# mainboard_edited_newer_edit_removed_most.net
KiCad netlist of a schematic drawn in EAGLE
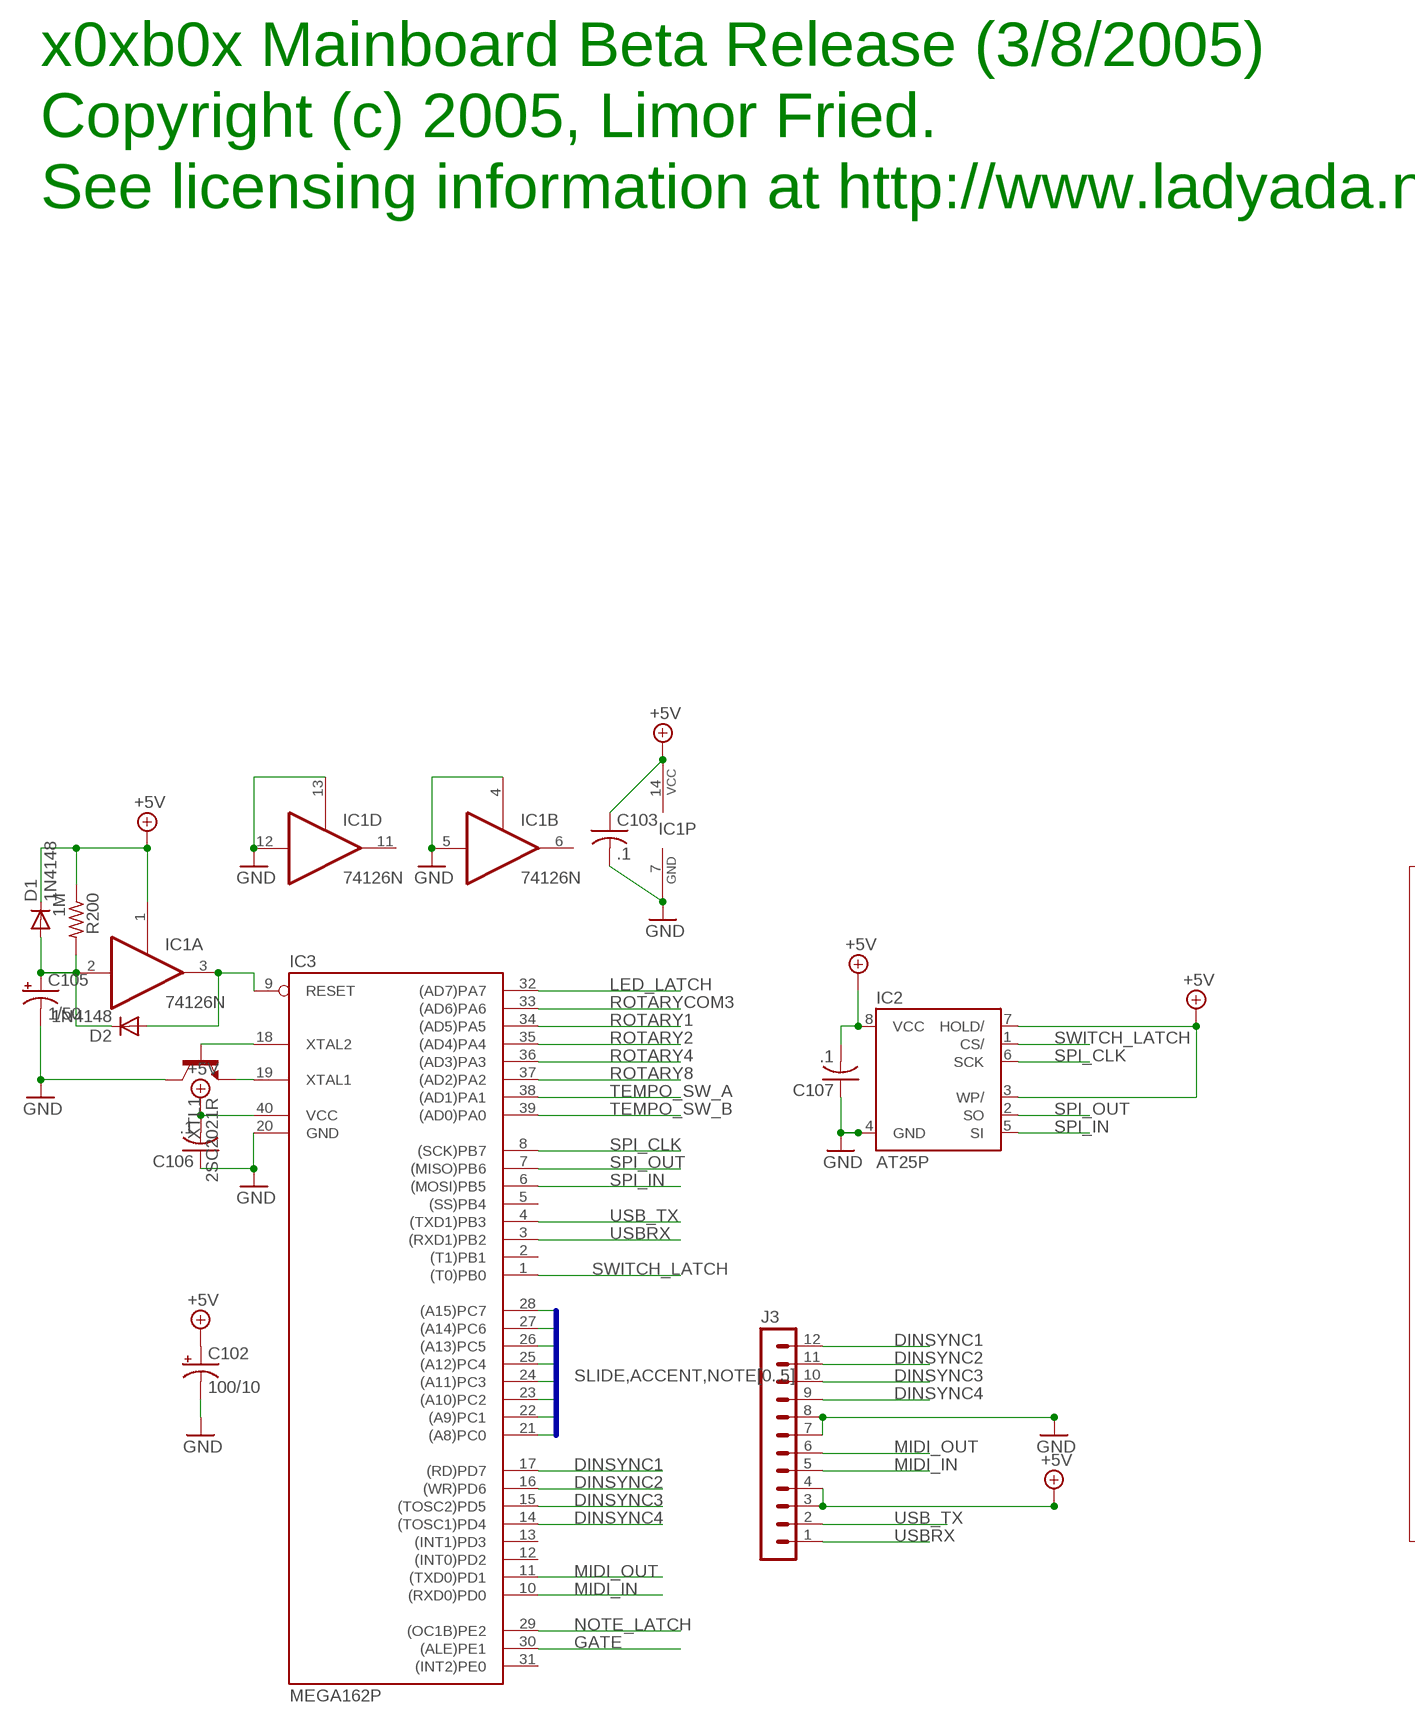
[diagram p0: schematic, sheet 1, part 1 of 3]
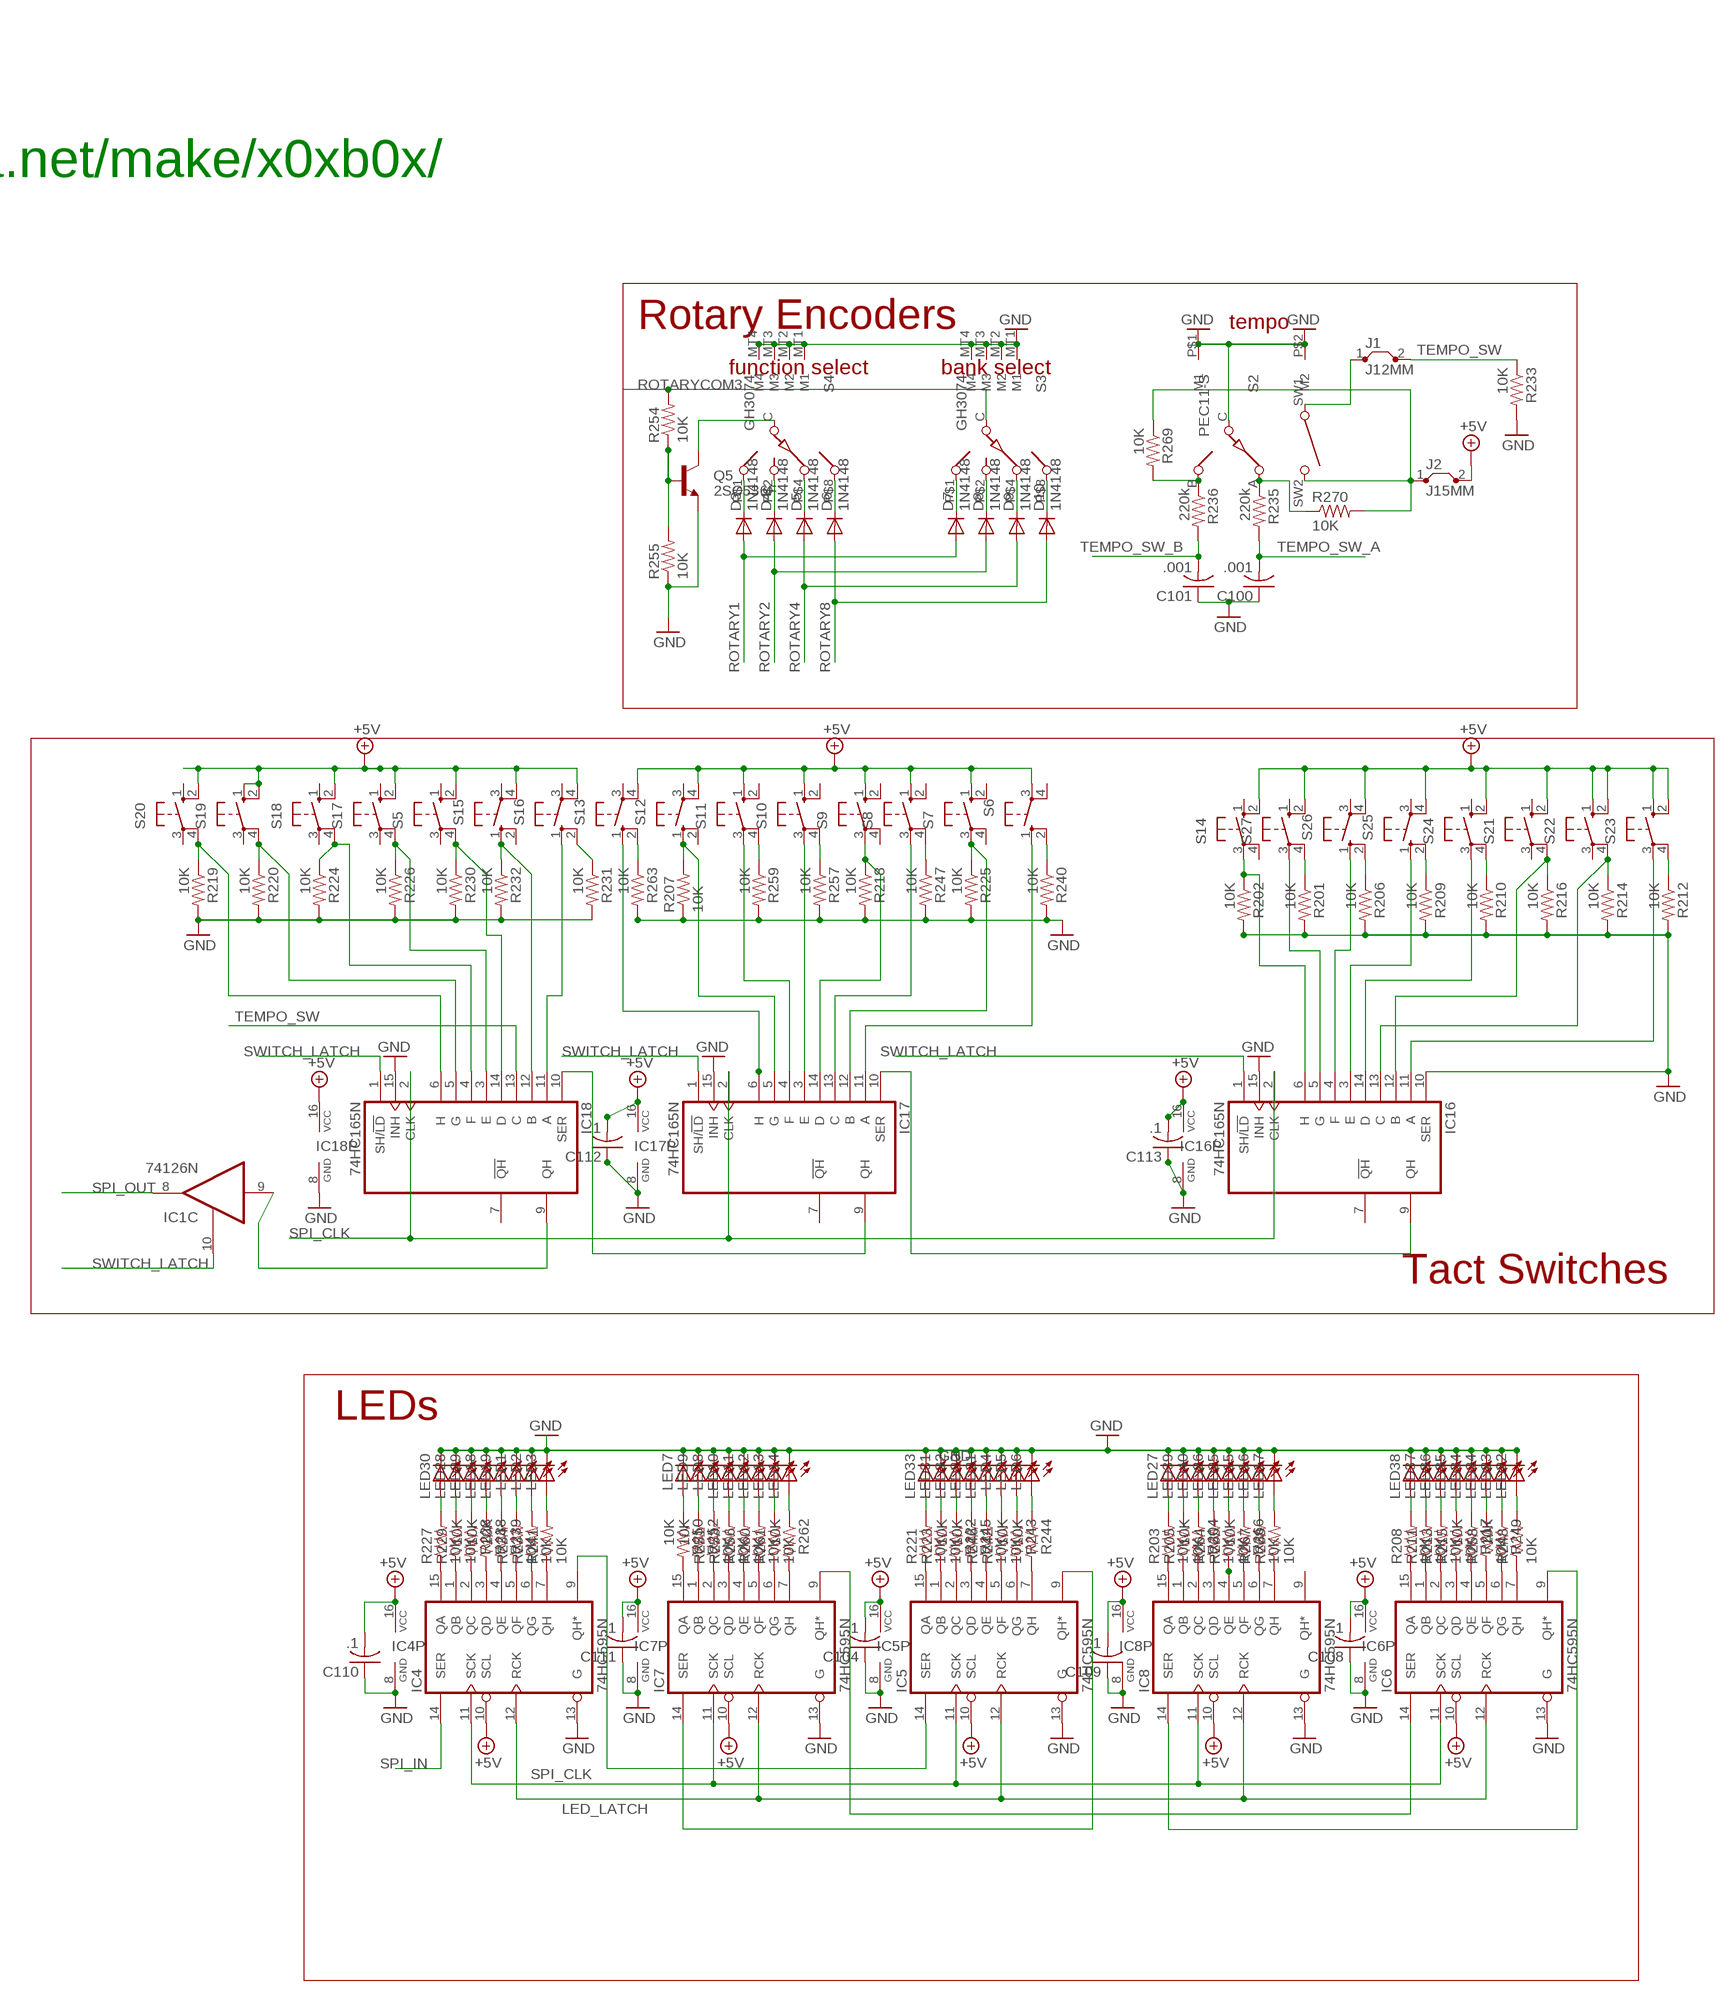
[diagram p1: schematic, sheet 1, part 2 of 3]
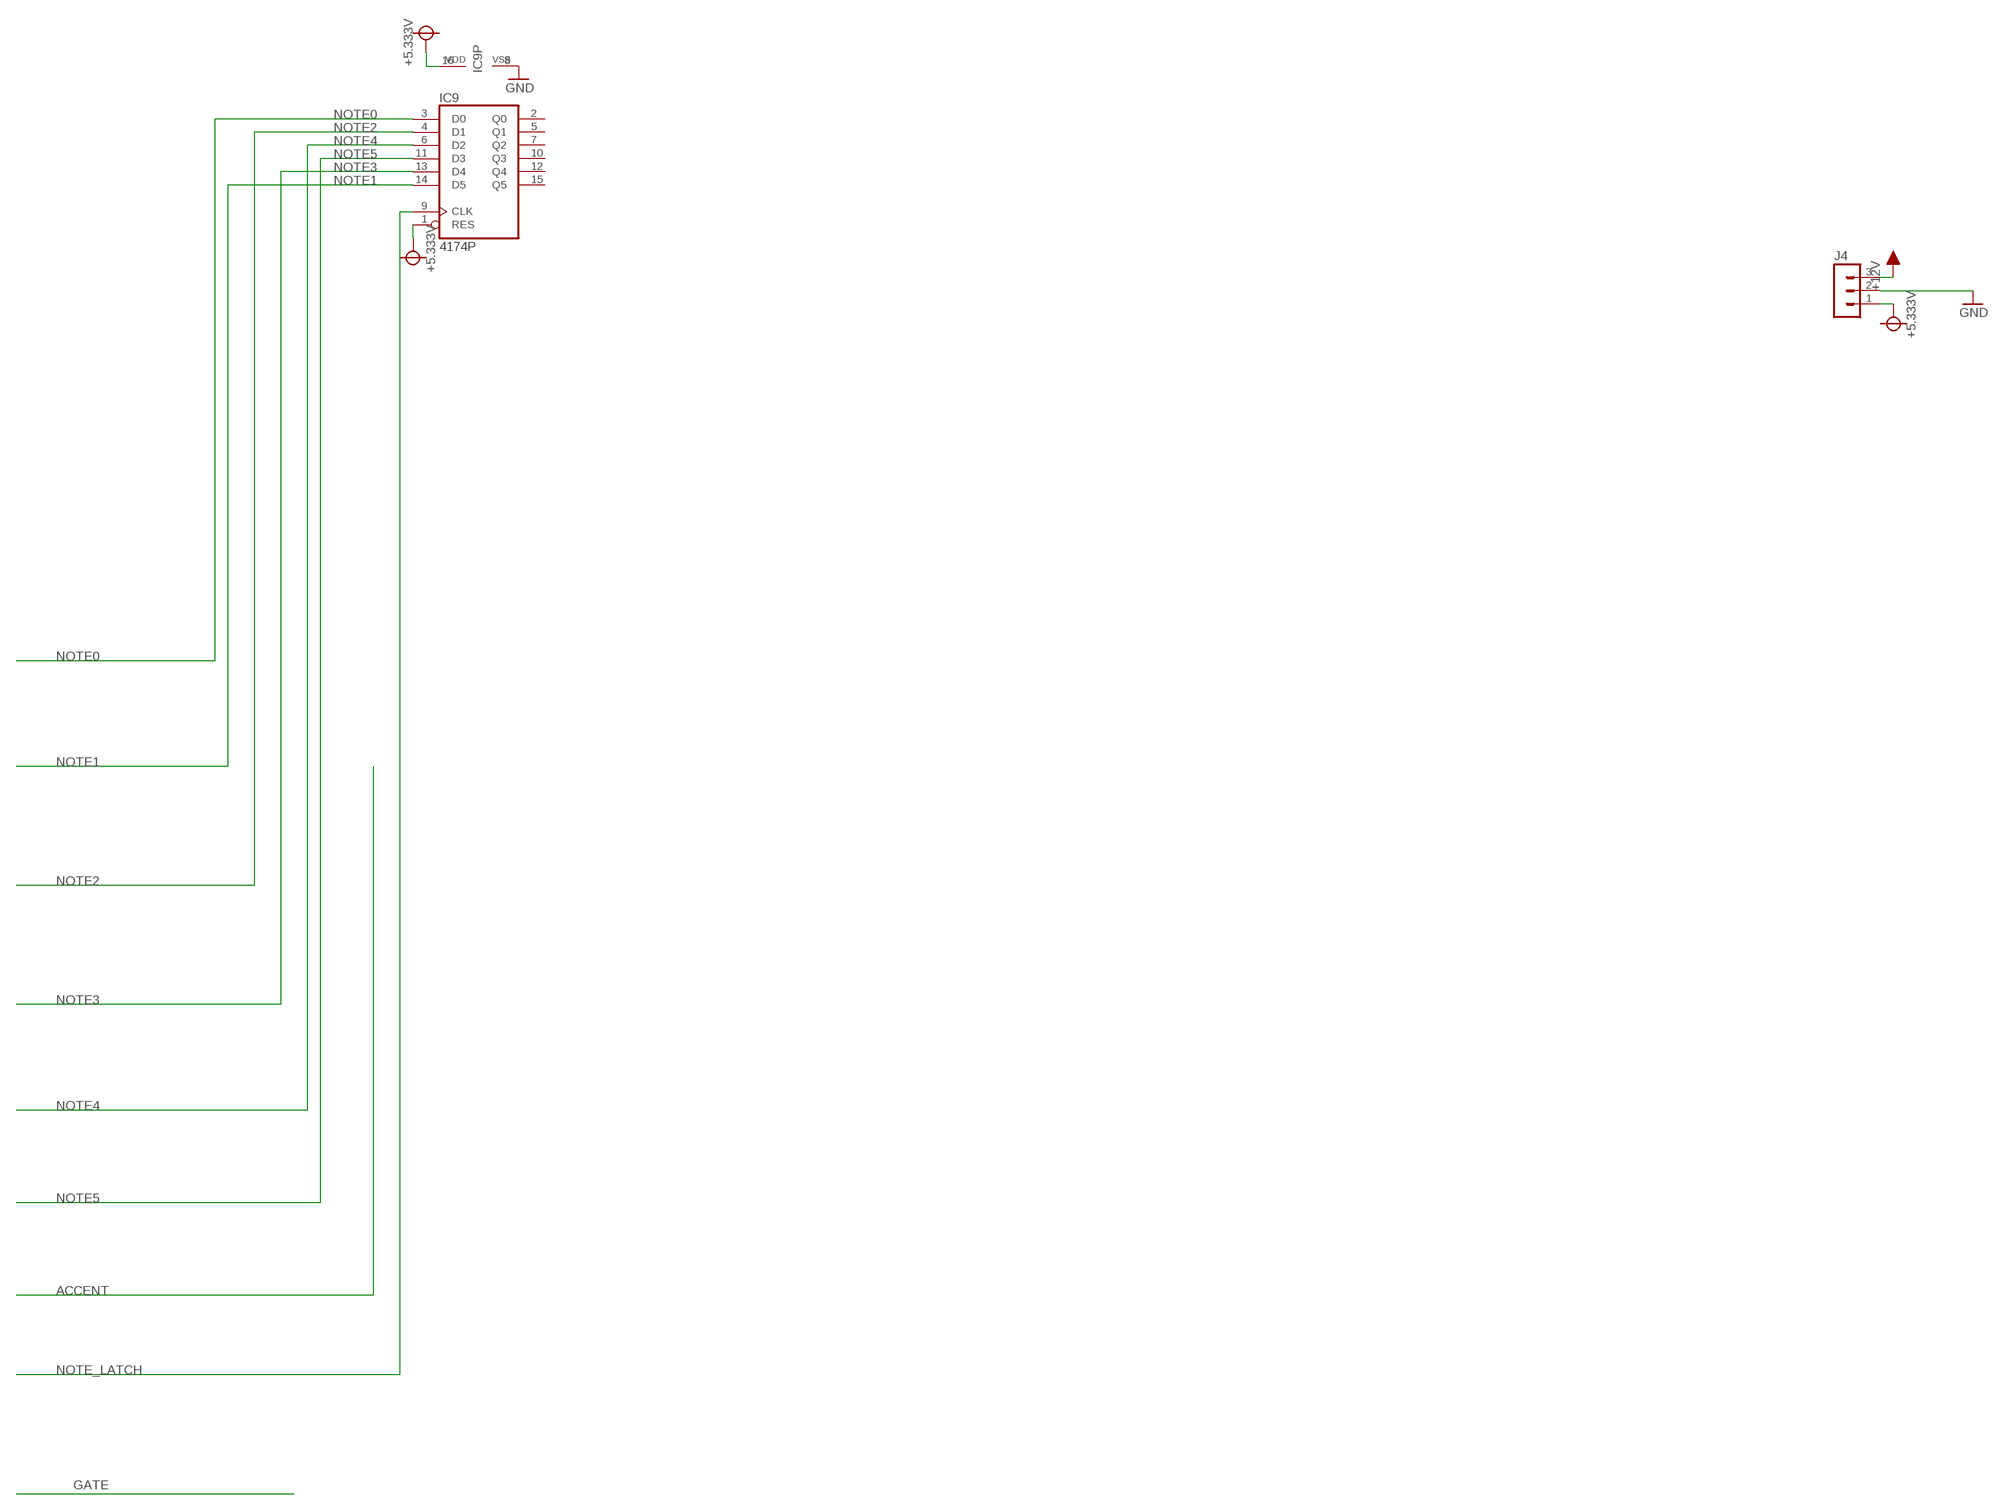
[diagram p2: schematic, sheet 1, part 3 of 3]

(export (version "E")
  (design (tool "Eeschema 10.0.6"))
  (components
    (comp (ref "C100")
      (value ".001")
      (footprint "eagle-import:C050-035X075")
      (libsource (lib "eagle-import") (part "C-US050-035X075"))
    )
    (comp (ref "C101")
      (value ".001")
      (footprint "eagle-import:C050-035X075")
      (libsource (lib "eagle-import") (part "C-US050-035X075"))
    )
    (comp (ref "C102")
      (value "100/10")
      (footprint "eagle-import:E5-6")
      (libsource (lib "eagle-import") (part "CPOL-USE5-6"))
    )
    (comp (ref "C103")
      (value ".1")
      (footprint "eagle-import:C050H075X075")
      (libsource (lib "eagle-import") (part "C-US050H075X075"))
    )
    (comp (ref "C104")
      (value ".1")
      (footprint "eagle-import:C050H075X075")
      (libsource (lib "eagle-import") (part "C-US050H075X075"))
    )
    (comp (ref "C105")
      (value "1/50")
      (footprint "eagle-import:E5-6")
      (libsource (lib "eagle-import") (part "CPOL-USE5-6"))
    )
    (comp (ref "C106")
      (value ".1")
      (footprint "eagle-import:C050H075X075")
      (libsource (lib "eagle-import") (part "C-US050H075X075"))
    )
    (comp (ref "C107")
      (value ".1")
      (footprint "eagle-import:C050H075X075")
      (libsource (lib "eagle-import") (part "C-US050H075X075"))
    )
    (comp (ref "C108")
      (value ".1")
      (footprint "eagle-import:C050H075X075")
      (libsource (lib "eagle-import") (part "C-US050H075X075"))
    )
    (comp (ref "C109")
      (value ".1")
      (footprint "eagle-import:C050H075X075")
      (libsource (lib "eagle-import") (part "C-US050H075X075"))
    )
    (comp (ref "C110")
      (value ".1")
      (footprint "eagle-import:C050H075X075")
      (libsource (lib "eagle-import") (part "C-US050H075X075"))
    )
    (comp (ref "C111")
      (value ".1")
      (footprint "eagle-import:C050H075X075")
      (libsource (lib "eagle-import") (part "C-US050H075X075"))
    )
    (comp (ref "C112")
      (value ".1")
      (footprint "eagle-import:C050H075X075")
      (libsource (lib "eagle-import") (part "C-US050H075X075"))
    )
    (comp (ref "C113")
      (value ".1")
      (footprint "eagle-import:C050H075X075")
      (libsource (lib "eagle-import") (part "C-US050H075X075"))
    )
    (comp (ref "D1")
      (value "1N4148")
      (footprint "eagle-import:DO35-10")
      (libsource (lib "eagle-import") (part "1N4148"))
    )
    (comp (ref "D2")
      (value "1N4148")
      (footprint "eagle-import:DO35-10")
      (libsource (lib "eagle-import") (part "1N4148"))
    )
    (comp (ref "D3")
      (value "1N4148")
      (footprint "eagle-import:DO35-10")
      (libsource (lib "eagle-import") (part "1N4148"))
    )
    (comp (ref "D4")
      (value "1N4148")
      (footprint "eagle-import:DO35-10")
      (libsource (lib "eagle-import") (part "1N4148"))
    )
    (comp (ref "D5")
      (value "1N4148")
      (footprint "eagle-import:DO35-10")
      (libsource (lib "eagle-import") (part "1N4148"))
    )
    (comp (ref "D6")
      (value "1N4148")
      (footprint "eagle-import:DO35-10")
      (libsource (lib "eagle-import") (part "1N4148"))
    )
    (comp (ref "D7")
      (value "1N4148")
      (footprint "eagle-import:DO35-10")
      (libsource (lib "eagle-import") (part "1N4148"))
    )
    (comp (ref "D8")
      (value "1N4148")
      (footprint "eagle-import:DO35-10")
      (libsource (lib "eagle-import") (part "1N4148"))
    )
    (comp (ref "D9")
      (value "1N4148")
      (footprint "eagle-import:DO35-10")
      (libsource (lib "eagle-import") (part "1N4148"))
    )
    (comp (ref "D10")
      (value "1N4148")
      (footprint "eagle-import:DO35-10")
      (libsource (lib "eagle-import") (part "1N4148"))
    )
    (comp (ref "IC1")
      (value "74126N")
      (footprint "eagle-import:DIL14")
      (libsource (lib "eagle-import") (part "74126N"))
    )
    (comp (ref "IC2")
      (value "AT25P")
      (footprint "eagle-import:DIL08")
      (libsource (lib "eagle-import") (part "AT25P"))
    )
    (comp (ref "IC3")
      (value "MEGA162P")
      (footprint "eagle-import:DIL40")
      (libsource (lib "eagle-import") (part "MEGA162P"))
    )
    (comp (ref "IC4")
      (value "74HC595N")
      (footprint "eagle-import:DIL16")
      (libsource (lib "eagle-import") (part "74595NHC"))
    )
    (comp (ref "IC5")
      (value "74HC595N")
      (footprint "eagle-import:DIL16")
      (libsource (lib "eagle-import") (part "74595NHC"))
    )
    (comp (ref "IC6")
      (value "74HC595N")
      (footprint "eagle-import:DIL16")
      (libsource (lib "eagle-import") (part "74595NHC"))
    )
    (comp (ref "IC7")
      (value "74HC595N")
      (footprint "eagle-import:DIL16")
      (libsource (lib "eagle-import") (part "74595NHC"))
    )
    (comp (ref "IC8")
      (value "74HC595N")
      (footprint "eagle-import:DIL16")
      (libsource (lib "eagle-import") (part "74595NHC"))
    )
    (comp (ref "IC9")
      (value "4174P")
      (footprint "eagle-import:DIL16")
      (libsource (lib "eagle-import") (part "4174P"))
    )
    (comp (ref "IC16")
      (value "74HC165N")
      (footprint "eagle-import:DIL16")
      (libsource (lib "eagle-import") (part "74165NHC"))
    )
    (comp (ref "IC17")
      (value "74HC165N")
      (footprint "eagle-import:DIL16")
      (libsource (lib "eagle-import") (part "74165NHC"))
    )
    (comp (ref "IC18")
      (value "74HC165N")
      (footprint "eagle-import:DIL16")
      (libsource (lib "eagle-import") (part "74165NHC"))
    )
    (comp (ref "J1")
      (value "J12MM")
      (footprint "eagle-import:12")
      (libsource (lib "eagle-import") (part "J12MM"))
    )
    (comp (ref "J2")
      (value "J15MM")
      (footprint "eagle-import:15")
      (libsource (lib "eagle-import") (part "J15MM"))
    )
    (comp (ref "J3")
      (value "MA12-1")
      (footprint "eagle-import:MA12-1")
      (libsource (lib "eagle-import") (part "MA12-1"))
    )
    (comp (ref "J4")
      (value "MA03-1")
      (footprint "eagle-import:MA03-1")
      (libsource (lib "eagle-import") (part "MA03-1"))
    )
    (comp (ref "LED1")
      (value "LED5MM")
      (footprint "eagle-import:LED5MM")
      (libsource (lib "eagle-import") (part "LED5MM"))
    )
    (comp (ref "LED2")
      (value "LED5MM")
      (footprint "eagle-import:LED5MM")
      (libsource (lib "eagle-import") (part "LED5MM"))
    )
    (comp (ref "LED3")
      (value "LED5MM")
      (footprint "eagle-import:LED5MM")
      (libsource (lib "eagle-import") (part "LED5MM"))
    )
    (comp (ref "LED4")
      (value "LED5MM")
      (footprint "eagle-import:LED5MM")
      (libsource (lib "eagle-import") (part "LED5MM"))
    )
    (comp (ref "LED5")
      (value "LED5MM")
      (footprint "eagle-import:LED5MM")
      (libsource (lib "eagle-import") (part "LED5MM"))
    )
    (comp (ref "LED6")
      (value "LED5MM")
      (footprint "eagle-import:LED5MM")
      (libsource (lib "eagle-import") (part "LED5MM"))
    )
    (comp (ref "LED7")
      (value "LED5MM")
      (footprint "eagle-import:LED5MM")
      (libsource (lib "eagle-import") (part "LED5MM"))
    )
    (comp (ref "LED8")
      (value "LED5MM")
      (footprint "eagle-import:LED5MM")
      (libsource (lib "eagle-import") (part "LED5MM"))
    )
    (comp (ref "LED9")
      (value "LED5MM")
      (footprint "eagle-import:LED5MM")
      (libsource (lib "eagle-import") (part "LED5MM"))
    )
    (comp (ref "LED10")
      (value "LED5MM")
      (footprint "eagle-import:LED5MM")
      (libsource (lib "eagle-import") (part "LED5MM"))
    )
    (comp (ref "LED11")
      (value "LED5MM")
      (footprint "eagle-import:LED5MM")
      (libsource (lib "eagle-import") (part "LED5MM"))
    )
    (comp (ref "LED12")
      (value "LED5MM")
      (footprint "eagle-import:LED5MM")
      (libsource (lib "eagle-import") (part "LED5MM"))
    )
    (comp (ref "LED13")
      (value "LED5MM")
      (footprint "eagle-import:LED5MM")
      (libsource (lib "eagle-import") (part "LED5MM"))
    )
    (comp (ref "LED14")
      (value "LED5MM")
      (footprint "eagle-import:LED5MM")
      (libsource (lib "eagle-import") (part "LED5MM"))
    )
    (comp (ref "LED15")
      (value "LED5MM")
      (footprint "eagle-import:LED5MM")
      (libsource (lib "eagle-import") (part "LED5MM"))
    )
    (comp (ref "LED16")
      (value "LED5MM")
      (footprint "eagle-import:LED5MM")
      (libsource (lib "eagle-import") (part "LED5MM"))
    )
    (comp (ref "LED17")
      (value "LED5MM")
      (footprint "eagle-import:LED5MM")
      (libsource (lib "eagle-import") (part "LED5MM"))
    )
    (comp (ref "LED18")
      (value "LED5MM")
      (footprint "eagle-import:LED5MM")
      (libsource (lib "eagle-import") (part "LED5MM"))
    )
    (comp (ref "LED19")
      (value "LED5MM")
      (footprint "eagle-import:LED5MM")
      (libsource (lib "eagle-import") (part "LED5MM"))
    )
    (comp (ref "LED20")
      (value "LED5MM")
      (footprint "eagle-import:LED5MM")
      (libsource (lib "eagle-import") (part "LED5MM"))
    )
    (comp (ref "LED21")
      (value "LED5MM")
      (footprint "eagle-import:LED5MM")
      (libsource (lib "eagle-import") (part "LED5MM"))
    )
    (comp (ref "LED22")
      (value "LED5MM")
      (footprint "eagle-import:LED5MM")
      (libsource (lib "eagle-import") (part "LED5MM"))
    )
    (comp (ref "LED23")
      (value "LED5MM")
      (footprint "eagle-import:LED5MM")
      (libsource (lib "eagle-import") (part "LED5MM"))
    )
    (comp (ref "LED24")
      (value "LED5MM")
      (footprint "eagle-import:LED5MM")
      (libsource (lib "eagle-import") (part "LED5MM"))
    )
    (comp (ref "LED25")
      (value "LED5MM")
      (footprint "eagle-import:LED5MM")
      (libsource (lib "eagle-import") (part "LED5MM"))
    )
    (comp (ref "LED26")
      (value "LED5MM")
      (footprint "eagle-import:LED5MM")
      (libsource (lib "eagle-import") (part "LED5MM"))
    )
    (comp (ref "LED27")
      (value "LED5MM")
      (footprint "eagle-import:LED5MM")
      (libsource (lib "eagle-import") (part "LED5MM"))
    )
    (comp (ref "LED28")
      (value "LED5MM")
      (footprint "eagle-import:LED5MM")
      (libsource (lib "eagle-import") (part "LED5MM"))
    )
    (comp (ref "LED29")
      (value "LED5MM")
      (footprint "eagle-import:LED5MM")
      (libsource (lib "eagle-import") (part "LED5MM"))
    )
    (comp (ref "LED30")
      (value "LED5MM")
      (footprint "eagle-import:LED5MM")
      (libsource (lib "eagle-import") (part "LED5MM"))
    )
    (comp (ref "LED31")
      (value "LED5MM")
      (footprint "eagle-import:LED5MM")
      (libsource (lib "eagle-import") (part "LED5MM"))
    )
    (comp (ref "LED32")
      (value "LED5MM")
      (footprint "eagle-import:LED5MM")
      (libsource (lib "eagle-import") (part "LED5MM"))
    )
    (comp (ref "LED33")
      (value "LED5MM")
      (footprint "eagle-import:LED5MM")
      (libsource (lib "eagle-import") (part "LED5MM"))
    )
    (comp (ref "LED34")
      (value "LED5MM")
      (footprint "eagle-import:LED5MM")
      (libsource (lib "eagle-import") (part "LED5MM"))
    )
    (comp (ref "LED35")
      (value "LED5MM")
      (footprint "eagle-import:LED5MM")
      (libsource (lib "eagle-import") (part "LED5MM"))
    )
    (comp (ref "LED36")
      (value "LED5MM")
      (footprint "eagle-import:LED5MM")
      (libsource (lib "eagle-import") (part "LED5MM"))
    )
    (comp (ref "LED37")
      (value "LED5MM")
      (footprint "eagle-import:LED5MM")
      (libsource (lib "eagle-import") (part "LED5MM"))
    )
    (comp (ref "LED38")
      (value "LED5MM")
      (footprint "eagle-import:LED5MM")
      (libsource (lib "eagle-import") (part "LED5MM"))
    )
    (comp (ref "LED39")
      (value "LED5MM")
      (footprint "eagle-import:LED5MM")
      (libsource (lib "eagle-import") (part "LED5MM"))
    )
    (comp (ref "LED40")
      (value "LED5MM")
      (footprint "eagle-import:LED5MM")
      (libsource (lib "eagle-import") (part "LED5MM"))
    )
    (comp (ref "Q5")
      (value "2SC536F")
      (footprint "eagle-import:2SC536F")
      (libsource (lib "eagle-import") (part "2SC536F"))
    )
    (comp (ref "R200")
      (value "1M")
      (footprint "eagle-import:0207_5V")
      (libsource (lib "eagle-import") (part "R-US_0207/5V"))
    )
    (comp (ref "R201")
      (value "10K")
      (footprint "eagle-import:0207_5V")
      (libsource (lib "eagle-import") (part "R-US_0207/5V"))
    )
    (comp (ref "R202")
      (value "10K")
      (footprint "eagle-import:0207_5V")
      (libsource (lib "eagle-import") (part "R-US_0207/5V"))
    )
    (comp (ref "R203")
      (value "10K")
      (footprint "eagle-import:0207_5V")
      (libsource (lib "eagle-import") (part "R-US_0207/5V"))
    )
    (comp (ref "R204")
      (value "10K")
      (footprint "eagle-import:0207_5V")
      (libsource (lib "eagle-import") (part "R-US_0207/5V"))
    )
    (comp (ref "R205")
      (value "10K")
      (footprint "eagle-import:0207_5V")
      (libsource (lib "eagle-import") (part "R-US_0207/5V"))
    )
    (comp (ref "R206")
      (value "10K")
      (footprint "eagle-import:0207_5V")
      (libsource (lib "eagle-import") (part "R-US_0207/5V"))
    )
    (comp (ref "R207")
      (value "10K")
      (footprint "eagle-import:0207_5V")
      (libsource (lib "eagle-import") (part "R-US_0207/5V"))
    )
    (comp (ref "R208")
      (value "10K")
      (footprint "eagle-import:0207_5V")
      (libsource (lib "eagle-import") (part "R-US_0207/5V"))
    )
    (comp (ref "R209")
      (value "10K")
      (footprint "eagle-import:0207_5V")
      (libsource (lib "eagle-import") (part "R-US_0207/5V"))
    )
    (comp (ref "R210")
      (value "10K")
      (footprint "eagle-import:0207_5V")
      (libsource (lib "eagle-import") (part "R-US_0207/5V"))
    )
    (comp (ref "R211")
      (value "10K")
      (footprint "eagle-import:0207_5V")
      (libsource (lib "eagle-import") (part "R-US_0207/5V"))
    )
    (comp (ref "R212")
      (value "10K")
      (footprint "eagle-import:0207_5V")
      (libsource (lib "eagle-import") (part "R-US_0207/5V"))
    )
    (comp (ref "R213")
      (value "10K")
      (footprint "eagle-import:0207_5V")
      (libsource (lib "eagle-import") (part "R-US_0207/5V"))
    )
    (comp (ref "R214")
      (value "10K")
      (footprint "eagle-import:0207_5V")
      (libsource (lib "eagle-import") (part "R-US_0207/5V"))
    )
    (comp (ref "R215")
      (value "10K")
      (footprint "eagle-import:0207_5V")
      (libsource (lib "eagle-import") (part "R-US_0207/5V"))
    )
    (comp (ref "R216")
      (value "10K")
      (footprint "eagle-import:0207_5V")
      (libsource (lib "eagle-import") (part "R-US_0207/5V"))
    )
    (comp (ref "R217")
      (value "10K")
      (footprint "eagle-import:0207_5V")
      (libsource (lib "eagle-import") (part "R-US_0207/5V"))
    )
    (comp (ref "R218")
      (value "10K")
      (footprint "eagle-import:0207_5V")
      (libsource (lib "eagle-import") (part "R-US_0207/5V"))
    )
    (comp (ref "R219")
      (value "10K")
      (footprint "eagle-import:0207_5V")
      (libsource (lib "eagle-import") (part "R-US_0207/5V"))
    )
    (comp (ref "R220")
      (value "10K")
      (footprint "eagle-import:0207_5V")
      (libsource (lib "eagle-import") (part "R-US_0207/5V"))
    )
    (comp (ref "R221")
      (value "10K")
      (footprint "eagle-import:0207_5V")
      (libsource (lib "eagle-import") (part "R-US_0207/5V"))
    )
    (comp (ref "R222")
      (value "10K")
      (footprint "eagle-import:0207_5V")
      (libsource (lib "eagle-import") (part "R-US_0207/5V"))
    )
    (comp (ref "R223")
      (value "10K")
      (footprint "eagle-import:0207_5V")
      (libsource (lib "eagle-import") (part "R-US_0207/5V"))
    )
    (comp (ref "R224")
      (value "10K")
      (footprint "eagle-import:0207_5V")
      (libsource (lib "eagle-import") (part "R-US_0207/5V"))
    )
    (comp (ref "R225")
      (value "10K")
      (footprint "eagle-import:0207_5V")
      (libsource (lib "eagle-import") (part "R-US_0207/5V"))
    )
    (comp (ref "R226")
      (value "10K")
      (footprint "eagle-import:0207_5V")
      (libsource (lib "eagle-import") (part "R-US_0207/5V"))
    )
    (comp (ref "R227")
      (value "10K")
      (footprint "eagle-import:0207_5V")
      (libsource (lib "eagle-import") (part "R-US_0207/5V"))
    )
    (comp (ref "R228")
      (value "10K")
      (footprint "eagle-import:0207_5V")
      (libsource (lib "eagle-import") (part "R-US_0207/5V"))
    )
    (comp (ref "R229")
      (value "10K")
      (footprint "eagle-import:0207_5V")
      (libsource (lib "eagle-import") (part "R-US_0207/5V"))
    )
    (comp (ref "R230")
      (value "10K")
      (footprint "eagle-import:0207_5V")
      (libsource (lib "eagle-import") (part "R-US_0207/5V"))
    )
    (comp (ref "R231")
      (value "10K")
      (footprint "eagle-import:0207_5V")
      (libsource (lib "eagle-import") (part "R-US_0207/5V"))
    )
    (comp (ref "R232")
      (value "10K")
      (footprint "eagle-import:0207_10")
      (libsource (lib "eagle-import") (part "R-US_0207/10"))
    )
    (comp (ref "R233")
      (value "10K")
      (footprint "eagle-import:0207_5V")
      (libsource (lib "eagle-import") (part "R-US_0207/5V"))
    )
    (comp (ref "R234")
      (value "10K")
      (footprint "eagle-import:0207_15")
      (libsource (lib "eagle-import") (part "R-US_0207/15"))
    )
    (comp (ref "R235")
      (value "220k")
      (footprint "eagle-import:0207_5V")
      (libsource (lib "eagle-import") (part "R-US_0207/5V"))
    )
    (comp (ref "R236")
      (value "220k")
      (footprint "eagle-import:0207_5V")
      (libsource (lib "eagle-import") (part "R-US_0207/5V"))
    )
    (comp (ref "R237")
      (value "10K")
      (footprint "eagle-import:0207_5V")
      (libsource (lib "eagle-import") (part "R-US_0207/5V"))
    )
    (comp (ref "R238")
      (value "10K")
      (footprint "eagle-import:0207_5V")
      (libsource (lib "eagle-import") (part "R-US_0207/5V"))
    )
    (comp (ref "R239")
      (value "10K")
      (footprint "eagle-import:0207_5V")
      (libsource (lib "eagle-import") (part "R-US_0207/5V"))
    )
    (comp (ref "R240")
      (value "10K")
      (footprint "eagle-import:0207_5V")
      (libsource (lib "eagle-import") (part "R-US_0207/5V"))
    )
    (comp (ref "R241")
      (value "10K")
      (footprint "eagle-import:0207_5V")
      (libsource (lib "eagle-import") (part "R-US_0207/5V"))
    )
    (comp (ref "R242")
      (value "10K")
      (footprint "eagle-import:0207_5V")
      (libsource (lib "eagle-import") (part "R-US_0207/5V"))
    )
    (comp (ref "R243")
      (value "10K")
      (footprint "eagle-import:0207_5V")
      (libsource (lib "eagle-import") (part "R-US_0207/5V"))
    )
    (comp (ref "R244")
      (value "10K")
      (footprint "eagle-import:0207_5V")
      (libsource (lib "eagle-import") (part "R-US_0207/5V"))
    )
    (comp (ref "R245")
      (value "10K")
      (footprint "eagle-import:0207_5V")
      (libsource (lib "eagle-import") (part "R-US_0207/5V"))
    )
    (comp (ref "R246")
      (value "10K")
      (footprint "eagle-import:0207_5V")
      (libsource (lib "eagle-import") (part "R-US_0207/5V"))
    )
    (comp (ref "R247")
      (value "10K")
      (footprint "eagle-import:0207_5V")
      (libsource (lib "eagle-import") (part "R-US_0207/5V"))
    )
    (comp (ref "R248")
      (value "10K")
      (footprint "eagle-import:0207_5V")
      (libsource (lib "eagle-import") (part "R-US_0207/5V"))
    )
    (comp (ref "R249")
      (value "10K")
      (footprint "eagle-import:0207_5V")
      (libsource (lib "eagle-import") (part "R-US_0207/5V"))
    )
    (comp (ref "R250")
      (value "10K")
      (footprint "eagle-import:0207_5V")
      (libsource (lib "eagle-import") (part "R-US_0207/5V"))
    )
    (comp (ref "R251")
      (value "10K")
      (footprint "eagle-import:0207_5V")
      (libsource (lib "eagle-import") (part "R-US_0207/5V"))
    )
    (comp (ref "R252")
      (value "10K")
      (footprint "eagle-import:0207_5V")
      (libsource (lib "eagle-import") (part "R-US_0207/5V"))
    )
    (comp (ref "R253")
      (value "10K")
      (footprint "eagle-import:0207_5V")
      (libsource (lib "eagle-import") (part "R-US_0207/5V"))
    )
    (comp (ref "R254")
      (value "10K")
      (footprint "eagle-import:0207_5V")
      (libsource (lib "eagle-import") (part "R-US_0207/5V"))
    )
    (comp (ref "R255")
      (value "10K")
      (footprint "eagle-import:0207_5V")
      (libsource (lib "eagle-import") (part "R-US_0207/5V"))
    )
    (comp (ref "R256")
      (value "10K")
      (footprint "eagle-import:0207_5V")
      (libsource (lib "eagle-import") (part "R-US_0207/5V"))
    )
    (comp (ref "R257")
      (value "10K")
      (footprint "eagle-import:0207_5V")
      (libsource (lib "eagle-import") (part "R-US_0207/5V"))
    )
    (comp (ref "R258")
      (value "10K")
      (footprint "eagle-import:0207_5V")
      (libsource (lib "eagle-import") (part "R-US_0207/5V"))
    )
    (comp (ref "R259")
      (value "10K")
      (footprint "eagle-import:0207_5V")
      (libsource (lib "eagle-import") (part "R-US_0207/5V"))
    )
    (comp (ref "R260")
      (value "10K")
      (footprint "eagle-import:0207_5V")
      (libsource (lib "eagle-import") (part "R-US_0207/5V"))
    )
    (comp (ref "R261")
      (value "10K")
      (footprint "eagle-import:0207_5V")
      (libsource (lib "eagle-import") (part "R-US_0207/5V"))
    )
    (comp (ref "R262")
      (value "10K")
      (footprint "eagle-import:0207_5V")
      (libsource (lib "eagle-import") (part "R-US_0207/5V"))
    )
    (comp (ref "R263")
      (value "10K")
      (footprint "eagle-import:0207_5V")
      (libsource (lib "eagle-import") (part "R-US_0207/5V"))
    )
    (comp (ref "R264")
      (value "10K")
      (footprint "eagle-import:0207_5V")
      (libsource (lib "eagle-import") (part "R-US_0207/5V"))
    )
    (comp (ref "R265")
      (value "10K")
      (footprint "eagle-import:0207_5V")
      (libsource (lib "eagle-import") (part "R-US_0207/5V"))
    )
    (comp (ref "R266")
      (value "10K")
      (footprint "eagle-import:0207_5V")
      (libsource (lib "eagle-import") (part "R-US_0207/5V"))
    )
    (comp (ref "R267")
      (value "10K")
      (footprint "eagle-import:0207_5V")
      (libsource (lib "eagle-import") (part "R-US_0207/5V"))
    )
    (comp (ref "R268")
      (value "10K")
      (footprint "eagle-import:0207_5V")
      (libsource (lib "eagle-import") (part "R-US_0207/5V"))
    )
    (comp (ref "R269")
      (value "10K")
      (footprint "eagle-import:0207_5V")
      (libsource (lib "eagle-import") (part "R-US_0207/5V"))
    )
    (comp (ref "R270")
      (value "10K")
      (footprint "eagle-import:0207_5V")
      (libsource (lib "eagle-import") (part "R-US_0207/5V"))
    )
    (comp (ref "S2")
      (value "PEC11-S")
      (footprint "eagle-import:PEC11-S")
      (libsource (lib "eagle-import") (part "PEC11-S"))
    )
    (comp (ref "S3")
      (value "GH3074")
      (footprint "eagle-import:GH3074")
      (libsource (lib "eagle-import") (part "GH3074"))
    )
    (comp (ref "S4")
      (value "GH3074")
      (footprint "eagle-import:GH3074")
      (libsource (lib "eagle-import") (part "GH3074"))
    )
    (comp (ref "S5")
      (value "40-XX")
      (footprint "eagle-import:B3F-40XX")
      (libsource (lib "eagle-import") (part "40-XX"))
    )
    (comp (ref "S6")
      (value "40-XX")
      (footprint "eagle-import:B3F-40XX")
      (libsource (lib "eagle-import") (part "40-XX"))
    )
    (comp (ref "S7")
      (value "40-XX")
      (footprint "eagle-import:B3F-40XX")
      (libsource (lib "eagle-import") (part "40-XX"))
    )
    (comp (ref "S8")
      (value "40-XX")
      (footprint "eagle-import:B3F-40XX")
      (libsource (lib "eagle-import") (part "40-XX"))
    )
    (comp (ref "S9")
      (value "40-XX")
      (footprint "eagle-import:B3F-40XX")
      (libsource (lib "eagle-import") (part "40-XX"))
    )
    (comp (ref "S10")
      (value "40-XX")
      (footprint "eagle-import:B3F-40XX")
      (libsource (lib "eagle-import") (part "40-XX"))
    )
    (comp (ref "S11")
      (value "40-XX")
      (footprint "eagle-import:B3F-40XX")
      (libsource (lib "eagle-import") (part "40-XX"))
    )
    (comp (ref "S12")
      (value "40-XX")
      (footprint "eagle-import:B3F-40XX")
      (libsource (lib "eagle-import") (part "40-XX"))
    )
    (comp (ref "S13")
      (value "40-XX")
      (footprint "eagle-import:B3F-40XX")
      (libsource (lib "eagle-import") (part "40-XX"))
    )
    (comp (ref "S14")
      (value "40-XX")
      (footprint "eagle-import:B3F-40XX")
      (libsource (lib "eagle-import") (part "40-XX"))
    )
    (comp (ref "S15")
      (value "40-XX")
      (footprint "eagle-import:B3F-40XX")
      (libsource (lib "eagle-import") (part "40-XX"))
    )
    (comp (ref "S16")
      (value "40-XX")
      (footprint "eagle-import:B3F-40XX")
      (libsource (lib "eagle-import") (part "40-XX"))
    )
    (comp (ref "S17")
      (value "40-XX")
      (footprint "eagle-import:B3F-40XX")
      (libsource (lib "eagle-import") (part "40-XX"))
    )
    (comp (ref "S18")
      (value "40-XX")
      (footprint "eagle-import:B3F-40XX")
      (libsource (lib "eagle-import") (part "40-XX"))
    )
    (comp (ref "S19")
      (value "40-XX")
      (footprint "eagle-import:B3F-40XX")
      (libsource (lib "eagle-import") (part "40-XX"))
    )
    (comp (ref "S20")
      (value "40-XX")
      (footprint "eagle-import:B3F-40XX")
      (libsource (lib "eagle-import") (part "40-XX"))
    )
    (comp (ref "S21")
      (value "40-XX")
      (footprint "eagle-import:B3F-40XX")
      (libsource (lib "eagle-import") (part "40-XX"))
    )
    (comp (ref "S22")
      (value "40-XX")
      (footprint "eagle-import:B3F-40XX")
      (libsource (lib "eagle-import") (part "40-XX"))
    )
    (comp (ref "S23")
      (value "40-XX")
      (footprint "eagle-import:B3F-40XX")
      (libsource (lib "eagle-import") (part "40-XX"))
    )
    (comp (ref "S24")
      (value "40-XX")
      (footprint "eagle-import:B3F-40XX")
      (libsource (lib "eagle-import") (part "40-XX"))
    )
    (comp (ref "S25")
      (value "40-XX")
      (footprint "eagle-import:B3F-40XX")
      (libsource (lib "eagle-import") (part "40-XX"))
    )
    (comp (ref "S26")
      (value "40-XX")
      (footprint "eagle-import:B3F-40XX")
      (libsource (lib "eagle-import") (part "40-XX"))
    )
    (comp (ref "S27")
      (value "40-XX")
      (footprint "eagle-import:B3F-40XX")
      (libsource (lib "eagle-import") (part "40-XX"))
    )
    (comp (ref "XTL1")
      (value "2SC2021R")
      (footprint "eagle-import:2SC2021")
      (libsource (lib "eagle-import") (part "2SC2021R"))
    )
  )
  (nets
    (net (code "7") (name "+5.333V") (class "Default")
      (node (ref "IC9") (pin "1") (pinfunction "RES_1") (pintype "input"))
      (node (ref "IC9") (pin "16") (pinfunction "VDD_16") (pintype "power_in"))
      (node (ref "J4") (pin "1") (pinfunction "1_1") (pintype "passive"))
    )
    (net (code "8") (name "+5V") (class "Default")
      (node (ref "C102") (pin "+") (pinfunction "+_+") (pintype "passive"))
      (node (ref "C103") (pin "1") (pinfunction "1_1") (pintype "passive"))
      (node (ref "C104") (pin "2") (pinfunction "2_2") (pintype "passive"))
      (node (ref "C106") (pin "2") (pinfunction "2_2") (pintype "passive"))
      (node (ref "C107") (pin "2") (pinfunction "2_2") (pintype "passive"))
      (node (ref "C108") (pin "2") (pinfunction "2_2") (pintype "passive"))
      (node (ref "C109") (pin "2") (pinfunction "2_2") (pintype "passive"))
      (node (ref "C110") (pin "2") (pinfunction "2_2") (pintype "passive"))
      (node (ref "C111") (pin "2") (pinfunction "2_2") (pintype "passive"))
      (node (ref "C112") (pin "2") (pinfunction "2_2") (pintype "passive"))
      (node (ref "C113") (pin "2") (pinfunction "2_2") (pintype "passive"))
      (node (ref "D1") (pin "C") (pinfunction "C_C") (pintype "passive"))
      (node (ref "IC1") (pin "1") (pinfunction "OE_1") (pintype "input"))
      (node (ref "IC1") (pin "14") (pinfunction "VCC_14") (pintype "power_in"))
      (node (ref "IC16") (pin "16") (pinfunction "VCC_16") (pintype "power_in"))
      (node (ref "IC17") (pin "16") (pinfunction "VCC_16") (pintype "power_in"))
      (node (ref "IC18") (pin "16") (pinfunction "VCC_16") (pintype "power_in"))
      (node (ref "IC2") (pin "3") (pinfunction "WP/_3") (pintype "input"))
      (node (ref "IC2") (pin "7") (pinfunction "HOLD/_7") (pintype "input"))
      (node (ref "IC2") (pin "8") (pinfunction "VCC_8") (pintype "power_in"))
      (node (ref "IC3") (pin "40") (pinfunction "VCC_40") (pintype "power_in"))
      (node (ref "IC4") (pin "10") (pinfunction "SCL_10") (pintype "input"))
      (node (ref "IC4") (pin "16") (pinfunction "VCC_16") (pintype "power_in"))
      (node (ref "IC5") (pin "10") (pinfunction "SCL_10") (pintype "input"))
      (node (ref "IC5") (pin "16") (pinfunction "VCC_16") (pintype "power_in"))
      (node (ref "IC6") (pin "10") (pinfunction "SCL_10") (pintype "input"))
      (node (ref "IC6") (pin "16") (pinfunction "VCC_16") (pintype "power_in"))
      (node (ref "IC7") (pin "10") (pinfunction "SCL_10") (pintype "input"))
      (node (ref "IC7") (pin "16") (pinfunction "VCC_16") (pintype "power_in"))
      (node (ref "IC8") (pin "10") (pinfunction "SCL_10") (pintype "input"))
      (node (ref "IC8") (pin "16") (pinfunction "VCC_16") (pintype "power_in"))
      (node (ref "J2") (pin "2") (pinfunction "2_2") (pintype "passive"))
      (node (ref "J3") (pin "3") (pinfunction "3_3") (pintype "passive"))
      (node (ref "J3") (pin "4") (pinfunction "4_4") (pintype "passive"))
      (node (ref "R200") (pin "1") (pinfunction "1_1") (pintype "passive"))
      (node (ref "S10") (pin "1") (pinfunction "S_1") (pintype "passive"))
      (node (ref "S11") (pin "1") (pinfunction "S_1") (pintype "passive"))
      (node (ref "S12") (pin "4") (pinfunction "P1_4") (pintype "passive"))
      (node (ref "S13") (pin "4") (pinfunction "P1_4") (pintype "passive"))
      (node (ref "S14") (pin "2") (pinfunction "S1_2") (pintype "passive"))
      (node (ref "S15") (pin "4") (pinfunction "P1_4") (pintype "passive"))
      (node (ref "S16") (pin "4") (pinfunction "P1_4") (pintype "passive"))
      (node (ref "S17") (pin "2") (pinfunction "S1_2") (pintype "passive"))
      (node (ref "S18") (pin "2") (pinfunction "S1_2") (pintype "passive"))
      (node (ref "S19") (pin "1") (pinfunction "S_1") (pintype "passive"))
      (node (ref "S19") (pin "2") (pinfunction "S1_2") (pintype "passive"))
      (node (ref "S20") (pin "2") (pinfunction "S1_2") (pintype "passive"))
      (node (ref "S21") (pin "2") (pinfunction "S1_2") (pintype "passive"))
      (node (ref "S22") (pin "1") (pinfunction "S_1") (pintype "passive"))
      (node (ref "S22") (pin "2") (pinfunction "S1_2") (pintype "passive"))
      (node (ref "S23") (pin "1") (pinfunction "S_1") (pintype "passive"))
      (node (ref "S23") (pin "2") (pinfunction "S1_2") (pintype "passive"))
      (node (ref "S24") (pin "2") (pinfunction "S1_2") (pintype "passive"))
      (node (ref "S25") (pin "4") (pinfunction "P1_4") (pintype "passive"))
      (node (ref "S26") (pin "4") (pinfunction "P1_4") (pintype "passive"))
      (node (ref "S27") (pin "2") (pinfunction "S1_2") (pintype "passive"))
      (node (ref "S5") (pin "2") (pinfunction "S1_2") (pintype "passive"))
      (node (ref "S6") (pin "3") (pinfunction "P_3") (pintype "passive"))
      (node (ref "S7") (pin "1") (pinfunction "S_1") (pintype "passive"))
      (node (ref "S8") (pin "1") (pinfunction "S_1") (pintype "passive"))
      (node (ref "S9") (pin "1") (pinfunction "S_1") (pintype "passive"))
    )
    (net (code "9") (name "+12V") (class "Default")
      (node (ref "J4") (pin "3") (pinfunction "3_3") (pintype "passive"))
    )
    (net (code "10") (name "/ACCENT") (class "Default")
      (node (ref "IC3") (pin "28") (pinfunction "(A15)PC7_28") (pintype "bidirectional"))
    )
    (net (code "11") (name "/DINSYNC1") (class "Default")
      (node (ref "IC3") (pin "17") (pinfunction "(RD)PD7_17") (pintype "bidirectional"))
      (node (ref "J3") (pin "12") (pinfunction "12_12") (pintype "passive"))
    )
    (net (code "12") (name "/DINSYNC2") (class "Default")
      (node (ref "IC3") (pin "16") (pinfunction "(WR)PD6_16") (pintype "bidirectional"))
      (node (ref "J3") (pin "11") (pinfunction "11_11") (pintype "passive"))
    )
    (net (code "13") (name "/DINSYNC3") (class "Default")
      (node (ref "IC3") (pin "15") (pinfunction "(TOSC2)PD5_15") (pintype "bidirectional"))
      (node (ref "J3") (pin "10") (pinfunction "10_10") (pintype "passive"))
    )
    (net (code "14") (name "/DINSYNC4") (class "Default")
      (node (ref "IC3") (pin "14") (pinfunction "(TOSC1)PD4_14") (pintype "bidirectional"))
      (node (ref "J3") (pin "9") (pinfunction "9_9") (pintype "passive"))
    )
    (net (code "15") (name "/GATE") (class "Default")
      (node (ref "IC3") (pin "30") (pinfunction "(ALE)PE1_30") (pintype "bidirectional"))
    )
    (net (code "16") (name "/LED_LATCH") (class "Default")
      (node (ref "IC3") (pin "32") (pinfunction "(AD7)PA7_32") (pintype "bidirectional"))
      (node (ref "IC4") (pin "12") (pinfunction "RCK_12") (pintype "input"))
      (node (ref "IC5") (pin "12") (pinfunction "RCK_12") (pintype "input"))
      (node (ref "IC6") (pin "12") (pinfunction "RCK_12") (pintype "input"))
      (node (ref "IC7") (pin "12") (pinfunction "RCK_12") (pintype "input"))
      (node (ref "IC8") (pin "12") (pinfunction "RCK_12") (pintype "input"))
    )
    (net (code "17") (name "/MIDI_IN") (class "Default")
      (node (ref "IC3") (pin "10") (pinfunction "(RXD0)PD0_10") (pintype "bidirectional"))
      (node (ref "J3") (pin "5") (pinfunction "5_5") (pintype "passive"))
    )
    (net (code "18") (name "/MIDI_OUT") (class "Default")
      (node (ref "IC3") (pin "11") (pinfunction "(TXD0)PD1_11") (pintype "bidirectional"))
      (node (ref "J3") (pin "6") (pinfunction "6_6") (pintype "passive"))
    )
    (net (code "19") (name "/NOTE0") (class "Default")
      (node (ref "IC3") (pin "21") (pinfunction "(A8)PC0_21") (pintype "bidirectional"))
      (node (ref "IC9") (pin "3") (pinfunction "D0_3") (pintype "input"))
    )
    (net (code "20") (name "/NOTE1") (class "Default")
      (node (ref "IC3") (pin "22") (pinfunction "(A9)PC1_22") (pintype "bidirectional"))
      (node (ref "IC9") (pin "14") (pinfunction "D5_14") (pintype "input"))
    )
    (net (code "21") (name "/NOTE2") (class "Default")
      (node (ref "IC3") (pin "23") (pinfunction "(A10)PC2_23") (pintype "bidirectional"))
      (node (ref "IC9") (pin "4") (pinfunction "D1_4") (pintype "input"))
    )
    (net (code "22") (name "/NOTE3") (class "Default")
      (node (ref "IC3") (pin "24") (pinfunction "(A11)PC3_24") (pintype "bidirectional"))
      (node (ref "IC9") (pin "13") (pinfunction "D4_13") (pintype "input"))
    )
    (net (code "23") (name "/NOTE4") (class "Default")
      (node (ref "IC3") (pin "25") (pinfunction "(A12)PC4_25") (pintype "bidirectional"))
      (node (ref "IC9") (pin "6") (pinfunction "D2_6") (pintype "input"))
    )
    (net (code "24") (name "/NOTE5") (class "Default")
      (node (ref "IC3") (pin "26") (pinfunction "(A13)PC5_26") (pintype "bidirectional"))
      (node (ref "IC9") (pin "11") (pinfunction "D3_11") (pintype "input"))
    )
    (net (code "25") (name "/NOTE_LATCH") (class "Default")
      (node (ref "IC3") (pin "29") (pinfunction "(OC1B)PE2_29") (pintype "bidirectional"))
      (node (ref "IC9") (pin "9") (pinfunction "CLK_9") (pintype "input"))
    )
    (net (code "26") (name "/ROTARY1") (class "Default")
      (node (ref "D3") (pin "A") (pinfunction "A_A") (pintype "passive"))
      (node (ref "D7") (pin "A") (pinfunction "A_A") (pintype "passive"))
      (node (ref "IC3") (pin "34") (pinfunction "(AD5)PA5_34") (pintype "bidirectional"))
    )
    (net (code "27") (name "/ROTARY2") (class "Default")
      (node (ref "D4") (pin "A") (pinfunction "A_A") (pintype "passive"))
      (node (ref "D8") (pin "A") (pinfunction "A_A") (pintype "passive"))
      (node (ref "IC3") (pin "35") (pinfunction "(AD4)PA4_35") (pintype "bidirectional"))
    )
    (net (code "28") (name "/ROTARY4") (class "Default")
      (node (ref "D5") (pin "A") (pinfunction "A_A") (pintype "passive"))
      (node (ref "D9") (pin "A") (pinfunction "A_A") (pintype "passive"))
      (node (ref "IC3") (pin "36") (pinfunction "(AD3)PA3_36") (pintype "bidirectional"))
    )
    (net (code "29") (name "/ROTARY8") (class "Default")
      (node (ref "D10") (pin "A") (pinfunction "A_A") (pintype "passive"))
      (node (ref "D6") (pin "A") (pinfunction "A_A") (pintype "passive"))
      (node (ref "IC3") (pin "37") (pinfunction "(AD2)PA2_37") (pintype "bidirectional"))
    )
    (net (code "30") (name "/ROTARYCOM3") (class "Default")
      (node (ref "IC3") (pin "33") (pinfunction "(AD6)PA6_33") (pintype "bidirectional"))
      (node (ref "R254") (pin "2") (pinfunction "2_2") (pintype "passive"))
      (node (ref "S3") (pin "C") (pinfunction "C_C") (pintype "passive"))
    )
    (net (code "32") (name "/SPI_CLK") (class "Default")
      (node (ref "IC16") (pin "2") (pinfunction "CLK_2") (pintype "input"))
      (node (ref "IC17") (pin "2") (pinfunction "CLK_2") (pintype "input"))
      (node (ref "IC18") (pin "2") (pinfunction "CLK_2") (pintype "input"))
      (node (ref "IC2") (pin "6") (pinfunction "SCK_6") (pintype "bidirectional"))
      (node (ref "IC3") (pin "8") (pinfunction "(SCK)PB7_8") (pintype "bidirectional"))
      (node (ref "IC4") (pin "11") (pinfunction "SCK_11") (pintype "input"))
      (node (ref "IC5") (pin "11") (pinfunction "SCK_11") (pintype "input"))
      (node (ref "IC6") (pin "11") (pinfunction "SCK_11") (pintype "input"))
      (node (ref "IC7") (pin "11") (pinfunction "SCK_11") (pintype "input"))
      (node (ref "IC8") (pin "11") (pinfunction "SCK_11") (pintype "input"))
    )
    (net (code "33") (name "/SPI_IN") (class "Default")
      (node (ref "IC2") (pin "5") (pinfunction "SI_5") (pintype "bidirectional"))
      (node (ref "IC3") (pin "6") (pinfunction "(MOSI)PB5_6") (pintype "bidirectional"))
      (node (ref "IC4") (pin "14") (pinfunction "SER_14") (pintype "input"))
    )
    (net (code "34") (name "/SPI_OUT") (class "Default")
      (node (ref "IC1") (pin "8") (pinfunction "O_8") (pintype "output"))
      (node (ref "IC2") (pin "2") (pinfunction "SO_2") (pintype "input"))
      (node (ref "IC3") (pin "7") (pinfunction "(MISO)PB6_7") (pintype "bidirectional"))
    )
    (net (code "35") (name "/SWITCH_LATCH") (class "Default")
      (node (ref "IC1") (pin "10") (pinfunction "OE_10") (pintype "input"))
      (node (ref "IC16") (pin "1") (pinfunction "SH/~{LD}_1") (pintype "input"))
      (node (ref "IC17") (pin "1") (pinfunction "SH/~{LD}_1") (pintype "input"))
      (node (ref "IC18") (pin "1") (pinfunction "SH/~{LD}_1") (pintype "input"))
      (node (ref "IC2") (pin "1") (pinfunction "CS/_1") (pintype "input"))
      (node (ref "IC3") (pin "1") (pinfunction "(T0)PB0_1") (pintype "bidirectional"))
    )
    (net (code "36") (name "/TEMPO_SW") (class "Default")
      (node (ref "IC18") (pin "13") (pinfunction "C_13") (pintype "input"))
      (node (ref "J1") (pin "2") (pinfunction "2_2") (pintype "passive"))
      (node (ref "R233") (pin "1") (pinfunction "1_1") (pintype "passive"))
    )
    (net (code "37") (name "/TEMPO_SW_A") (class "Default")
      (node (ref "C100") (pin "2") (pinfunction "2_2") (pintype "passive"))
      (node (ref "IC3") (pin "38") (pinfunction "(AD1)PA1_38") (pintype "bidirectional"))
      (node (ref "R235") (pin "2") (pinfunction "2_2") (pintype "passive"))
    )
    (net (code "38") (name "/TEMPO_SW_B") (class "Default")
      (node (ref "C101") (pin "2") (pinfunction "2_2") (pintype "passive"))
      (node (ref "IC3") (pin "39") (pinfunction "(AD0)PA0_39") (pintype "bidirectional"))
      (node (ref "R236") (pin "2") (pinfunction "2_2") (pintype "passive"))
    )
    (net (code "39") (name "/USBRX") (class "Default")
      (node (ref "IC3") (pin "3") (pinfunction "(RXD1)PB2_3") (pintype "bidirectional"))
      (node (ref "J3") (pin "1") (pinfunction "1_1") (pintype "passive"))
    )
    (net (code "40") (name "/USB_TX") (class "Default")
      (node (ref "IC3") (pin "4") (pinfunction "(TXD1)PB3_4") (pintype "bidirectional"))
      (node (ref "J3") (pin "2") (pinfunction "2_2") (pintype "passive"))
    )
    (net (code "41") (name "GND") (class "Default")
      (node (ref "C100") (pin "1") (pinfunction "1_1") (pintype "passive"))
      (node (ref "C101") (pin "1") (pinfunction "1_1") (pintype "passive"))
      (node (ref "C102") (pin "-") (pinfunction "-_-") (pintype "passive"))
      (node (ref "C103") (pin "2") (pinfunction "2_2") (pintype "passive"))
      (node (ref "C104") (pin "1") (pinfunction "1_1") (pintype "passive"))
      (node (ref "C105") (pin "-") (pinfunction "-_-") (pintype "passive"))
      (node (ref "C106") (pin "1") (pinfunction "1_1") (pintype "passive"))
      (node (ref "C107") (pin "1") (pinfunction "1_1") (pintype "passive"))
      (node (ref "C108") (pin "1") (pinfunction "1_1") (pintype "passive"))
      (node (ref "C109") (pin "1") (pinfunction "1_1") (pintype "passive"))
      (node (ref "C110") (pin "1") (pinfunction "1_1") (pintype "passive"))
      (node (ref "C111") (pin "1") (pinfunction "1_1") (pintype "passive"))
      (node (ref "C112") (pin "1") (pinfunction "1_1") (pintype "passive"))
      (node (ref "C113") (pin "1") (pinfunction "1_1") (pintype "passive"))
      (node (ref "IC1") (pin "12") (pinfunction "I_12") (pintype "input"))
      (node (ref "IC1") (pin "13") (pinfunction "OE_13") (pintype "input"))
      (node (ref "IC1") (pin "4") (pinfunction "OE_4") (pintype "input"))
      (node (ref "IC1") (pin "5") (pinfunction "I_5") (pintype "input"))
      (node (ref "IC1") (pin "7") (pinfunction "GND_7") (pintype "power_in"))
      (node (ref "IC16") (pin "10") (pinfunction "SER_10") (pintype "input"))
      (node (ref "IC16") (pin "15") (pinfunction "INH_15") (pintype "input"))
      (node (ref "IC16") (pin "8") (pinfunction "GND_8") (pintype "power_in"))
      (node (ref "IC17") (pin "15") (pinfunction "INH_15") (pintype "input"))
      (node (ref "IC17") (pin "8") (pinfunction "GND_8") (pintype "power_in"))
      (node (ref "IC18") (pin "15") (pinfunction "INH_15") (pintype "input"))
      (node (ref "IC18") (pin "8") (pinfunction "GND_8") (pintype "power_in"))
      (node (ref "IC2") (pin "4") (pinfunction "GND_4") (pintype "power_in"))
      (node (ref "IC3") (pin "20") (pinfunction "GND_20") (pintype "power_in"))
      (node (ref "IC4") (pin "13") (pinfunction "G_13") (pintype "input"))
      (node (ref "IC4") (pin "8") (pinfunction "GND_8") (pintype "power_in"))
      (node (ref "IC5") (pin "13") (pinfunction "G_13") (pintype "input"))
      (node (ref "IC5") (pin "8") (pinfunction "GND_8") (pintype "power_in"))
      (node (ref "IC6") (pin "13") (pinfunction "G_13") (pintype "input"))
      (node (ref "IC6") (pin "8") (pinfunction "GND_8") (pintype "power_in"))
      (node (ref "IC7") (pin "13") (pinfunction "G_13") (pintype "input"))
      (node (ref "IC7") (pin "8") (pinfunction "GND_8") (pintype "power_in"))
      (node (ref "IC8") (pin "13") (pinfunction "G_13") (pintype "input"))
      (node (ref "IC8") (pin "8") (pinfunction "GND_8") (pintype "power_in"))
      (node (ref "IC9") (pin "8") (pinfunction "VSS_8") (pintype "power_in"))
      (node (ref "J3") (pin "7") (pinfunction "7_7") (pintype "passive"))
      (node (ref "J3") (pin "8") (pinfunction "8_8") (pintype "passive"))
      (node (ref "J4") (pin "2") (pinfunction "2_2") (pintype "passive"))
      (node (ref "LED1") (pin "K") (pinfunction "C_K") (pintype "passive"))
      (node (ref "LED10") (pin "K") (pinfunction "C_K") (pintype "passive"))
      (node (ref "LED11") (pin "K") (pinfunction "C_K") (pintype "passive"))
      (node (ref "LED12") (pin "K") (pinfunction "C_K") (pintype "passive"))
      (node (ref "LED13") (pin "K") (pinfunction "C_K") (pintype "passive"))
      (node (ref "LED14") (pin "K") (pinfunction "C_K") (pintype "passive"))
      (node (ref "LED15") (pin "K") (pinfunction "C_K") (pintype "passive"))
      (node (ref "LED16") (pin "K") (pinfunction "C_K") (pintype "passive"))
      (node (ref "LED17") (pin "K") (pinfunction "C_K") (pintype "passive"))
      (node (ref "LED18") (pin "K") (pinfunction "C_K") (pintype "passive"))
      (node (ref "LED19") (pin "K") (pinfunction "C_K") (pintype "passive"))
      (node (ref "LED2") (pin "K") (pinfunction "C_K") (pintype "passive"))
      (node (ref "LED20") (pin "K") (pinfunction "C_K") (pintype "passive"))
      (node (ref "LED21") (pin "K") (pinfunction "C_K") (pintype "passive"))
      (node (ref "LED22") (pin "K") (pinfunction "C_K") (pintype "passive"))
      (node (ref "LED23") (pin "K") (pinfunction "C_K") (pintype "passive"))
      (node (ref "LED24") (pin "K") (pinfunction "C_K") (pintype "passive"))
      (node (ref "LED25") (pin "K") (pinfunction "C_K") (pintype "passive"))
      (node (ref "LED26") (pin "K") (pinfunction "C_K") (pintype "passive"))
      (node (ref "LED27") (pin "K") (pinfunction "C_K") (pintype "passive"))
      (node (ref "LED28") (pin "K") (pinfunction "C_K") (pintype "passive"))
      (node (ref "LED29") (pin "K") (pinfunction "C_K") (pintype "passive"))
      (node (ref "LED3") (pin "K") (pinfunction "C_K") (pintype "passive"))
      (node (ref "LED30") (pin "K") (pinfunction "C_K") (pintype "passive"))
      (node (ref "LED31") (pin "K") (pinfunction "C_K") (pintype "passive"))
      (node (ref "LED32") (pin "K") (pinfunction "C_K") (pintype "passive"))
      (node (ref "LED33") (pin "K") (pinfunction "C_K") (pintype "passive"))
      (node (ref "LED34") (pin "K") (pinfunction "C_K") (pintype "passive"))
      (node (ref "LED35") (pin "K") (pinfunction "C_K") (pintype "passive"))
      (node (ref "LED36") (pin "K") (pinfunction "C_K") (pintype "passive"))
      (node (ref "LED37") (pin "K") (pinfunction "C_K") (pintype "passive"))
      (node (ref "LED38") (pin "K") (pinfunction "C_K") (pintype "passive"))
      (node (ref "LED39") (pin "K") (pinfunction "C_K") (pintype "passive"))
      (node (ref "LED4") (pin "K") (pinfunction "C_K") (pintype "passive"))
      (node (ref "LED40") (pin "K") (pinfunction "C_K") (pintype "passive"))
      (node (ref "LED5") (pin "K") (pinfunction "C_K") (pintype "passive"))
      (node (ref "LED6") (pin "K") (pinfunction "C_K") (pintype "passive"))
      (node (ref "LED7") (pin "K") (pinfunction "C_K") (pintype "passive"))
      (node (ref "LED8") (pin "K") (pinfunction "C_K") (pintype "passive"))
      (node (ref "LED9") (pin "K") (pinfunction "C_K") (pintype "passive"))
      (node (ref "Q5") (pin "3") (pinfunction "E_3") (pintype "passive"))
      (node (ref "R201") (pin "2") (pinfunction "2_2") (pintype "passive"))
      (node (ref "R202") (pin "2") (pinfunction "2_2") (pintype "passive"))
      (node (ref "R206") (pin "2") (pinfunction "2_2") (pintype "passive"))
      (node (ref "R207") (pin "1") (pinfunction "1_1") (pintype "passive"))
      (node (ref "R209") (pin "2") (pinfunction "2_2") (pintype "passive"))
      (node (ref "R210") (pin "2") (pinfunction "2_2") (pintype "passive"))
      (node (ref "R212") (pin "2") (pinfunction "2_2") (pintype "passive"))
      (node (ref "R214") (pin "2") (pinfunction "2_2") (pintype "passive"))
      (node (ref "R216") (pin "2") (pinfunction "2_2") (pintype "passive"))
      (node (ref "R218") (pin "2") (pinfunction "2_2") (pintype "passive"))
      (node (ref "R219") (pin "2") (pinfunction "2_2") (pintype "passive"))
      (node (ref "R220") (pin "2") (pinfunction "2_2") (pintype "passive"))
      (node (ref "R224") (pin "2") (pinfunction "2_2") (pintype "passive"))
      (node (ref "R225") (pin "2") (pinfunction "2_2") (pintype "passive"))
      (node (ref "R226") (pin "2") (pinfunction "2_2") (pintype "passive"))
      (node (ref "R230") (pin "2") (pinfunction "2_2") (pintype "passive"))
      (node (ref "R231") (pin "2") (pinfunction "2_2") (pintype "passive"))
      (node (ref "R232") (pin "2") (pinfunction "2_2") (pintype "passive"))
      (node (ref "R233") (pin "2") (pinfunction "2_2") (pintype "passive"))
      (node (ref "R240") (pin "2") (pinfunction "2_2") (pintype "passive"))
      (node (ref "R247") (pin "2") (pinfunction "2_2") (pintype "passive"))
      (node (ref "R255") (pin "1") (pinfunction "1_1") (pintype "passive"))
      (node (ref "R257") (pin "2") (pinfunction "2_2") (pintype "passive"))
      (node (ref "R259") (pin "2") (pinfunction "2_2") (pintype "passive"))
      (node (ref "R263") (pin "2") (pinfunction "2_2") (pintype "passive"))
      (node (ref "S2") (pin "C") (pinfunction "C_C") (pintype "passive"))
      (node (ref "S2") (pin "P$1") (pinfunction "M1_P$1") (pintype "passive"))
      (node (ref "S2") (pin "P$2") (pinfunction "M2_P$2") (pintype "passive"))
      (node (ref "S3") (pin "MT1") (pinfunction "M1_MT1") (pintype "passive"))
      (node (ref "S3") (pin "MT2") (pinfunction "M2_MT2") (pintype "passive"))
      (node (ref "S3") (pin "MT3") (pinfunction "M3_MT3") (pintype "passive"))
      (node (ref "S3") (pin "MT4") (pinfunction "M4_MT4") (pintype "passive"))
      (node (ref "S4") (pin "MT1") (pinfunction "M1_MT1") (pintype "passive"))
      (node (ref "S4") (pin "MT2") (pinfunction "M2_MT2") (pintype "passive"))
      (node (ref "S4") (pin "MT3") (pinfunction "M3_MT3") (pintype "passive"))
      (node (ref "S4") (pin "MT4") (pinfunction "M4_MT4") (pintype "passive"))
      (node (ref "XTL1") (pin "2") (pinfunction "C_2") (pintype "passive"))
    )
    (net (code "42") (name "Net-(IC1A-I)") (class "Default")
      (node (ref "C105") (pin "+") (pinfunction "+_+") (pintype "passive"))
      (node (ref "D1") (pin "A") (pinfunction "A_A") (pintype "passive"))
      (node (ref "D2") (pin "C") (pinfunction "C_C") (pintype "passive"))
      (node (ref "IC1") (pin "2") (pinfunction "I_2") (pintype "input"))
      (node (ref "R200") (pin "2") (pinfunction "2_2") (pintype "passive"))
    )
    (net (code "43") (name "Net-(IC1A-O)") (class "Default")
      (node (ref "D2") (pin "A") (pinfunction "A_A") (pintype "passive"))
      (node (ref "IC1") (pin "3") (pinfunction "O_3") (pintype "output"))
      (node (ref "IC3") (pin "9") (pinfunction "RESET_9") (pintype "input"))
    )
    (net (code "44") (name "Net-(IC3-XTAL1)") (class "Default")
      (node (ref "IC3") (pin "19") (pinfunction "XTAL1_19") (pintype "input"))
      (node (ref "XTL1") (pin "1") (pinfunction "E_1") (pintype "passive"))
    )
    (net (code "45") (name "Net-(IC3-XTAL2)") (class "Default")
      (node (ref "IC3") (pin "18") (pinfunction "XTAL2_18") (pintype "input"))
      (node (ref "XTL1") (pin "3") (pinfunction "B_3") (pintype "passive"))
    )
    (net (code "46") (name "Net-(IC4A-QA)") (class "Default")
      (node (ref "IC4") (pin "15") (pinfunction "QA_15") (pintype "tri_state"))
      (node (ref "R227") (pin "1") (pinfunction "1_1") (pintype "passive"))
    )
    (net (code "47") (name "Net-(IC4A-QB)") (class "Default")
      (node (ref "IC4") (pin "1") (pinfunction "QB_1") (pintype "tri_state"))
      (node (ref "R229") (pin "1") (pinfunction "1_1") (pintype "passive"))
    )
    (net (code "48") (name "Net-(IC4A-QC)") (class "Default")
      (node (ref "IC4") (pin "2") (pinfunction "QC_2") (pintype "tri_state"))
      (node (ref "R228") (pin "2") (pinfunction "2_2") (pintype "passive"))
    )
    (net (code "49") (name "Net-(IC4A-QD)") (class "Default")
      (node (ref "IC4") (pin "3") (pinfunction "QD_3") (pintype "tri_state"))
      (node (ref "R238") (pin "2") (pinfunction "2_2") (pintype "passive"))
    )
    (net (code "50") (name "Net-(IC4A-QE)") (class "Default")
      (node (ref "IC4") (pin "4") (pinfunction "QE_4") (pintype "tri_state"))
      (node (ref "R239") (pin "2") (pinfunction "2_2") (pintype "passive"))
    )
    (net (code "51") (name "Net-(IC4A-QF)") (class "Default")
      (node (ref "IC4") (pin "5") (pinfunction "QF_5") (pintype "tri_state"))
      (node (ref "R234") (pin "1") (pinfunction "1_1") (pintype "passive"))
    )
    (net (code "52") (name "Net-(IC4A-QG)") (class "Default")
      (node (ref "IC4") (pin "6") (pinfunction "QG_6") (pintype "tri_state"))
      (node (ref "R237") (pin "1") (pinfunction "1_1") (pintype "passive"))
    )
    (net (code "53") (name "Net-(IC4A-QH)") (class "Default")
      (node (ref "IC4") (pin "7") (pinfunction "QH_7") (pintype "tri_state"))
      (node (ref "R241") (pin "1") (pinfunction "1_1") (pintype "passive"))
    )
    (net (code "54") (name "Net-(IC4A-QH*)") (class "Default")
      (node (ref "IC4") (pin "9") (pinfunction "QH*_9") (pintype "tri_state"))
      (node (ref "IC5") (pin "14") (pinfunction "SER_14") (pintype "input"))
    )
    (net (code "55") (name "Net-(IC5A-QA)") (class "Default")
      (node (ref "IC5") (pin "15") (pinfunction "QA_15") (pintype "tri_state"))
      (node (ref "R221") (pin "1") (pinfunction "1_1") (pintype "passive"))
    )
    (net (code "56") (name "Net-(IC5A-QB)") (class "Default")
      (node (ref "IC5") (pin "1") (pinfunction "QB_1") (pintype "tri_state"))
      (node (ref "R223") (pin "1") (pinfunction "1_1") (pintype "passive"))
    )
    (net (code "57") (name "Net-(IC5A-QC)") (class "Default")
      (node (ref "IC5") (pin "2") (pinfunction "QC_2") (pintype "tri_state"))
      (node (ref "R222") (pin "2") (pinfunction "2_2") (pintype "passive"))
    )
    (net (code "58") (name "Net-(IC5A-QD)") (class "Default")
      (node (ref "IC5") (pin "3") (pinfunction "QD_3") (pintype "tri_state"))
      (node (ref "R245") (pin "2") (pinfunction "2_2") (pintype "passive"))
    )
    (net (code "59") (name "Net-(IC5A-QE)") (class "Default")
      (node (ref "IC5") (pin "4") (pinfunction "QE_4") (pintype "tri_state"))
      (node (ref "R246") (pin "1") (pinfunction "1_1") (pintype "passive"))
    )
    (net (code "60") (name "Net-(IC5A-QF)") (class "Default")
      (node (ref "IC5") (pin "5") (pinfunction "QF_5") (pintype "tri_state"))
      (node (ref "R242") (pin "1") (pinfunction "1_1") (pintype "passive"))
    )
    (net (code "61") (name "Net-(IC5A-QG)") (class "Default")
      (node (ref "IC5") (pin "6") (pinfunction "QG_6") (pintype "tri_state"))
      (node (ref "R243") (pin "2") (pinfunction "2_2") (pintype "passive"))
    )
    (net (code "62") (name "Net-(IC5A-QH)") (class "Default")
      (node (ref "IC5") (pin "7") (pinfunction "QH_7") (pintype "tri_state"))
      (node (ref "R244") (pin "2") (pinfunction "2_2") (pintype "passive"))
    )
    (net (code "63") (name "Net-(IC5A-QH*)") (class "Default")
      (node (ref "IC5") (pin "9") (pinfunction "QH*_9") (pintype "tri_state"))
      (node (ref "IC7") (pin "14") (pinfunction "SER_14") (pintype "input"))
    )
    (net (code "64") (name "Net-(IC6A-QA)") (class "Default")
      (node (ref "IC6") (pin "15") (pinfunction "QA_15") (pintype "tri_state"))
      (node (ref "R208") (pin "1") (pinfunction "1_1") (pintype "passive"))
    )
    (net (code "65") (name "Net-(IC6A-QB)") (class "Default")
      (node (ref "IC6") (pin "1") (pinfunction "QB_1") (pintype "tri_state"))
      (node (ref "R211") (pin "1") (pinfunction "1_1") (pintype "passive"))
    )
    (net (code "66") (name "Net-(IC6A-QC)") (class "Default")
      (node (ref "IC6") (pin "2") (pinfunction "QC_2") (pintype "tri_state"))
      (node (ref "R213") (pin "1") (pinfunction "1_1") (pintype "passive"))
    )
    (net (code "67") (name "Net-(IC6A-QD)") (class "Default")
      (node (ref "IC6") (pin "3") (pinfunction "QD_3") (pintype "tri_state"))
      (node (ref "R215") (pin "1") (pinfunction "1_1") (pintype "passive"))
    )
    (net (code "68") (name "Net-(IC6A-QE)") (class "Default")
      (node (ref "IC6") (pin "4") (pinfunction "QE_4") (pintype "tri_state"))
      (node (ref "R217") (pin "2") (pinfunction "2_2") (pintype "passive"))
    )
    (net (code "69") (name "Net-(IC6A-QF)") (class "Default")
      (node (ref "IC6") (pin "5") (pinfunction "QF_5") (pintype "tri_state"))
      (node (ref "R258") (pin "1") (pinfunction "1_1") (pintype "passive"))
    )
    (net (code "70") (name "Net-(IC6A-QG)") (class "Default")
      (node (ref "IC6") (pin "6") (pinfunction "QG_6") (pintype "tri_state"))
      (node (ref "R249") (pin "2") (pinfunction "2_2") (pintype "passive"))
    )
    (net (code "71") (name "Net-(IC6A-QH)") (class "Default")
      (node (ref "IC6") (pin "7") (pinfunction "QH_7") (pintype "tri_state"))
      (node (ref "R248") (pin "1") (pinfunction "1_1") (pintype "passive"))
    )
    (net (code "72") (name "Net-(IC6A-QH*)") (class "Default")
      (node (ref "IC6") (pin "9") (pinfunction "QH*_9") (pintype "tri_state"))
      (node (ref "IC8") (pin "14") (pinfunction "SER_14") (pintype "input"))
    )
    (net (code "73") (name "Net-(IC6A-SER)") (class "Default")
      (node (ref "IC6") (pin "14") (pinfunction "SER_14") (pintype "input"))
      (node (ref "IC7") (pin "9") (pinfunction "QH*_9") (pintype "tri_state"))
    )
    (net (code "74") (name "Net-(IC7A-QA)") (class "Default")
      (node (ref "IC7") (pin "15") (pinfunction "QA_15") (pintype "tri_state"))
      (node (ref "R250") (pin "2") (pinfunction "2_2") (pintype "passive"))
    )
    (net (code "75") (name "Net-(IC7A-QB)") (class "Default")
      (node (ref "IC7") (pin "1") (pinfunction "QB_1") (pintype "tri_state"))
      (node (ref "R252") (pin "2") (pinfunction "2_2") (pintype "passive"))
    )
    (net (code "76") (name "Net-(IC7A-QC)") (class "Default")
      (node (ref "IC7") (pin "2") (pinfunction "QC_2") (pintype "tri_state"))
      (node (ref "R251") (pin "1") (pinfunction "1_1") (pintype "passive"))
    )
    (net (code "77") (name "Net-(IC7A-QD)") (class "Default")
      (node (ref "IC7") (pin "3") (pinfunction "QD_3") (pintype "tri_state"))
      (node (ref "R253") (pin "1") (pinfunction "1_1") (pintype "passive"))
    )
    (net (code "78") (name "Net-(IC7A-QE)") (class "Default")
      (node (ref "IC7") (pin "4") (pinfunction "QE_4") (pintype "tri_state"))
      (node (ref "R256") (pin "1") (pinfunction "1_1") (pintype "passive"))
    )
    (net (code "79") (name "Net-(IC7A-QF)") (class "Default")
      (node (ref "IC7") (pin "5") (pinfunction "QF_5") (pintype "tri_state"))
      (node (ref "R260") (pin "1") (pinfunction "1_1") (pintype "passive"))
    )
    (net (code "80") (name "Net-(IC7A-QG)") (class "Default")
      (node (ref "IC7") (pin "6") (pinfunction "QG_6") (pintype "tri_state"))
      (node (ref "R261") (pin "1") (pinfunction "1_1") (pintype "passive"))
    )
    (net (code "81") (name "Net-(IC7A-QH)") (class "Default")
      (node (ref "IC7") (pin "7") (pinfunction "QH_7") (pintype "tri_state"))
      (node (ref "R262") (pin "2") (pinfunction "2_2") (pintype "passive"))
    )
    (net (code "82") (name "Net-(IC8A-QA)") (class "Default")
      (node (ref "IC8") (pin "15") (pinfunction "QA_15") (pintype "tri_state"))
      (node (ref "R203") (pin "1") (pinfunction "1_1") (pintype "passive"))
    )
    (net (code "83") (name "Net-(IC8A-QB)") (class "Default")
      (node (ref "IC8") (pin "1") (pinfunction "QB_1") (pintype "tri_state"))
      (node (ref "R205") (pin "1") (pinfunction "1_1") (pintype "passive"))
    )
    (net (code "84") (name "Net-(IC8A-QC)") (class "Default")
      (node (ref "IC8") (pin "2") (pinfunction "QC_2") (pintype "tri_state"))
      (node (ref "R204") (pin "2") (pinfunction "2_2") (pintype "passive"))
    )
    (net (code "85") (name "Net-(IC8A-QD)") (class "Default")
      (node (ref "IC8") (pin "3") (pinfunction "QD_3") (pintype "tri_state"))
      (node (ref "R264") (pin "1") (pinfunction "1_1") (pintype "passive"))
    )
    (net (code "86") (name "Net-(IC8A-QE)") (class "Default")
      (node (ref "IC8") (pin "4") (pinfunction "QE_4") (pintype "tri_state"))
      (node (ref "R265") (pin "1") (pinfunction "1_1") (pintype "passive"))
    )
    (net (code "87") (name "Net-(IC8A-QF)") (class "Default")
      (node (ref "IC8") (pin "5") (pinfunction "QF_5") (pintype "tri_state"))
      (node (ref "R266") (pin "2") (pinfunction "2_2") (pintype "passive"))
    )
    (net (code "88") (name "Net-(IC8A-QG)") (class "Default")
      (node (ref "IC8") (pin "6") (pinfunction "QG_6") (pintype "tri_state"))
      (node (ref "R267") (pin "1") (pinfunction "1_1") (pintype "passive"))
    )
    (net (code "89") (name "Net-(IC8A-QH)") (class "Default")
      (node (ref "IC8") (pin "7") (pinfunction "QH_7") (pintype "tri_state"))
      (node (ref "R268") (pin "1") (pinfunction "1_1") (pintype "passive"))
    )
    (net (code "90") (name "Net-(IC16A-A)") (class "Default")
      (node (ref "IC16") (pin "11") (pinfunction "A_11") (pintype "input"))
      (node (ref "S23") (pin "3") (pinfunction "P_3") (pintype "passive"))
    )
    (net (code "91") (name "Net-(IC16A-B)") (class "Default")
      (node (ref "IC16") (pin "12") (pinfunction "B_12") (pintype "input"))
      (node (ref "R216") (pin "1") (pinfunction "1_1") (pintype "passive"))
      (node (ref "S21") (pin "4") (pinfunction "P1_4") (pintype "passive"))
    )
    (net (code "92") (name "Net-(IC16A-C)") (class "Default")
      (node (ref "IC16") (pin "13") (pinfunction "C_13") (pintype "input"))
      (node (ref "R214") (pin "1") (pinfunction "1_1") (pintype "passive"))
      (node (ref "S22") (pin "4") (pinfunction "P1_4") (pintype "passive"))
    )
    (net (code "93") (name "Net-(IC16A-D)") (class "Default")
      (node (ref "IC16") (pin "14") (pinfunction "D_14") (pintype "input"))
      (node (ref "S24") (pin "3") (pinfunction "P_3") (pintype "passive"))
    )
    (net (code "94") (name "Net-(IC16A-E)") (class "Default")
      (node (ref "IC16") (pin "3") (pinfunction "E_3") (pintype "input"))
      (node (ref "S25") (pin "1") (pinfunction "S_1") (pintype "passive"))
    )
    (net (code "95") (name "Net-(IC16A-F)") (class "Default")
      (node (ref "IC16") (pin "4") (pinfunction "F_4") (pintype "input"))
      (node (ref "S26") (pin "1") (pinfunction "S_1") (pintype "passive"))
    )
    (net (code "96") (name "Net-(IC16A-G)") (class "Default")
      (node (ref "IC16") (pin "5") (pinfunction "G_5") (pintype "input"))
      (node (ref "S27") (pin "3") (pinfunction "P_3") (pintype "passive"))
    )
    (net (code "97") (name "Net-(IC16A-H)") (class "Default")
      (node (ref "IC16") (pin "6") (pinfunction "H_6") (pintype "input"))
      (node (ref "R202") (pin "1") (pinfunction "1_1") (pintype "passive"))
      (node (ref "S14") (pin "3") (pinfunction "P_3") (pintype "passive"))
    )
    (net (code "98") (name "Net-(IC16A-QH)") (class "Default")
      (node (ref "IC16") (pin "9") (pinfunction "QH_9") (pintype "output"))
      (node (ref "IC17") (pin "10") (pinfunction "SER_10") (pintype "input"))
    )
    (net (code "99") (name "Net-(IC17A-A)") (class "Default")
      (node (ref "IC17") (pin "11") (pinfunction "A_11") (pintype "input"))
      (node (ref "S6") (pin "1") (pinfunction "S_1") (pintype "passive"))
    )
    (net (code "100") (name "Net-(IC17A-B)") (class "Default")
      (node (ref "IC17") (pin "12") (pinfunction "B_12") (pintype "input"))
      (node (ref "R225") (pin "1") (pinfunction "1_1") (pintype "passive"))
      (node (ref "S7") (pin "3") (pinfunction "P_3") (pintype "passive"))
    )
    (net (code "101") (name "Net-(IC17A-C)") (class "Default")
      (node (ref "IC17") (pin "13") (pinfunction "C_13") (pintype "input"))
      (node (ref "S8") (pin "3") (pinfunction "P_3") (pintype "passive"))
    )
    (net (code "102") (name "Net-(IC17A-D)") (class "Default")
      (node (ref "IC17") (pin "14") (pinfunction "D_14") (pintype "input"))
      (node (ref "R218") (pin "1") (pinfunction "1_1") (pintype "passive"))
      (node (ref "S9") (pin "3") (pinfunction "P_3") (pintype "passive"))
    )
    (net (code "103") (name "Net-(IC17A-E)") (class "Default")
      (node (ref "IC17") (pin "3") (pinfunction "E_3") (pintype "input"))
      (node (ref "S10") (pin "3") (pinfunction "P_3") (pintype "passive"))
    )
    (net (code "104") (name "Net-(IC17A-F)") (class "Default")
      (node (ref "IC17") (pin "4") (pinfunction "F_4") (pintype "input"))
      (node (ref "S11") (pin "3") (pinfunction "P_3") (pintype "passive"))
    )
    (net (code "105") (name "Net-(IC17A-G)") (class "Default")
      (node (ref "IC17") (pin "5") (pinfunction "G_5") (pintype "input"))
      (node (ref "R207") (pin "2") (pinfunction "2_2") (pintype "passive"))
      (node (ref "S12") (pin "1") (pinfunction "S_1") (pintype "passive"))
    )
    (net (code "106") (name "Net-(IC17A-H)") (class "Default")
      (node (ref "IC17") (pin "6") (pinfunction "H_6") (pintype "input"))
      (node (ref "S13") (pin "1") (pinfunction "S_1") (pintype "passive"))
    )
    (net (code "107") (name "Net-(IC17A-QH)") (class "Default")
      (node (ref "IC17") (pin "9") (pinfunction "QH_9") (pintype "output"))
      (node (ref "IC18") (pin "10") (pinfunction "SER_10") (pintype "input"))
    )
    (net (code "108") (name "Net-(IC18A-A)") (class "Default")
      (node (ref "IC18") (pin "11") (pinfunction "A_11") (pintype "input"))
      (node (ref "S16") (pin "1") (pinfunction "S_1") (pintype "passive"))
    )
    (net (code "109") (name "Net-(IC18A-B)") (class "Default")
      (node (ref "IC18") (pin "12") (pinfunction "B_12") (pintype "input"))
      (node (ref "R232") (pin "1") (pinfunction "1_1") (pintype "passive"))
      (node (ref "S15") (pin "1") (pinfunction "S_1") (pintype "passive"))
    )
    (net (code "110") (name "Net-(IC18A-D)") (class "Default")
      (node (ref "IC18") (pin "14") (pinfunction "D_14") (pintype "input"))
      (node (ref "R230") (pin "1") (pinfunction "1_1") (pintype "passive"))
      (node (ref "S5") (pin "4") (pinfunction "P1_4") (pintype "passive"))
    )
    (net (code "111") (name "Net-(IC18A-E)") (class "Default")
      (node (ref "IC18") (pin "3") (pinfunction "E_3") (pintype "input"))
      (node (ref "R226") (pin "1") (pinfunction "1_1") (pintype "passive"))
      (node (ref "S17") (pin "4") (pinfunction "P1_4") (pintype "passive"))
    )
    (net (code "112") (name "Net-(IC18A-F)") (class "Default")
      (node (ref "IC18") (pin "4") (pinfunction "F_4") (pintype "input"))
      (node (ref "R224") (pin "1") (pinfunction "1_1") (pintype "passive"))
      (node (ref "S18") (pin "4") (pinfunction "P1_4") (pintype "passive"))
    )
    (net (code "113") (name "Net-(IC18A-G)") (class "Default")
      (node (ref "IC18") (pin "5") (pinfunction "G_5") (pintype "input"))
      (node (ref "R220") (pin "1") (pinfunction "1_1") (pintype "passive"))
      (node (ref "S19") (pin "4") (pinfunction "P1_4") (pintype "passive"))
    )
    (net (code "114") (name "Net-(IC18A-H)") (class "Default")
      (node (ref "IC18") (pin "6") (pinfunction "H_6") (pintype "input"))
      (node (ref "R219") (pin "1") (pinfunction "1_1") (pintype "passive"))
      (node (ref "S20") (pin "4") (pinfunction "P1_4") (pintype "passive"))
    )
    (net (code "115") (name "Net-(IC18A-QH)") (class "Default")
      (node (ref "IC1") (pin "9") (pinfunction "I_9") (pintype "input"))
      (node (ref "IC18") (pin "9") (pinfunction "QH_9") (pintype "output"))
    )
    (net (code "116") (name "Net-(J1-Pad1)") (class "Default")
      (node (ref "J1") (pin "1") (pinfunction "1_1") (pintype "passive"))
      (node (ref "S2") (pin "SW1") (pinfunction "SW1_SW1") (pintype "passive"))
    )
    (net (code "117") (name "Net-(J2-Pad1)") (class "Default")
      (node (ref "J2") (pin "1") (pinfunction "1_1") (pintype "passive"))
      (node (ref "R269") (pin "1") (pinfunction "1_1") (pintype "passive"))
      (node (ref "R270") (pin "2") (pinfunction "2_2") (pintype "passive"))
      (node (ref "S2") (pin "SW2") (pinfunction "SW2_SW2") (pintype "passive"))
    )
    (net (code "118") (name "Net-(LED1-PadA)") (class "Default")
      (node (ref "LED1") (pin "A") (pinfunction "A_A") (pintype "passive"))
      (node (ref "R234") (pin "2") (pinfunction "2_2") (pintype "passive"))
    )
    (net (code "119") (name "Net-(LED2-PadA)") (class "Default")
      (node (ref "LED2") (pin "A") (pinfunction "A_A") (pintype "passive"))
      (node (ref "R237") (pin "2") (pinfunction "2_2") (pintype "passive"))
    )
    (net (code "120") (name "Net-(LED3-PadA)") (class "Default")
      (node (ref "LED3") (pin "A") (pinfunction "A_A") (pintype "passive"))
      (node (ref "R241") (pin "2") (pinfunction "2_2") (pintype "passive"))
    )
    (net (code "121") (name "Net-(LED4-PadA)") (class "Default")
      (node (ref "LED4") (pin "A") (pinfunction "A_A") (pintype "passive"))
      (node (ref "R242") (pin "2") (pinfunction "2_2") (pintype "passive"))
    )
    (net (code "122") (name "Net-(LED5-PadA)") (class "Default")
      (node (ref "LED5") (pin "A") (pinfunction "A_A") (pintype "passive"))
      (node (ref "R243") (pin "1") (pinfunction "1_1") (pintype "passive"))
    )
    (net (code "123") (name "Net-(LED6-PadA)") (class "Default")
      (node (ref "LED6") (pin "A") (pinfunction "A_A") (pintype "passive"))
      (node (ref "R244") (pin "1") (pinfunction "1_1") (pintype "passive"))
    )
    (net (code "124") (name "Net-(LED7-PadA)") (class "Default")
      (node (ref "LED7") (pin "A") (pinfunction "A_A") (pintype "passive"))
      (node (ref "R250") (pin "1") (pinfunction "1_1") (pintype "passive"))
    )
    (net (code "125") (name "Net-(LED8-PadA)") (class "Default")
      (node (ref "LED8") (pin "A") (pinfunction "A_A") (pintype "passive"))
      (node (ref "R251") (pin "2") (pinfunction "2_2") (pintype "passive"))
    )
    (net (code "126") (name "Net-(LED9-PadA)") (class "Default")
      (node (ref "LED9") (pin "A") (pinfunction "A_A") (pintype "passive"))
      (node (ref "R252") (pin "1") (pinfunction "1_1") (pintype "passive"))
    )
    (net (code "127") (name "Net-(LED10-PadA)") (class "Default")
      (node (ref "LED10") (pin "A") (pinfunction "A_A") (pintype "passive"))
      (node (ref "R253") (pin "2") (pinfunction "2_2") (pintype "passive"))
    )
    (net (code "128") (name "Net-(LED11-PadA)") (class "Default")
      (node (ref "LED11") (pin "A") (pinfunction "A_A") (pintype "passive"))
      (node (ref "R256") (pin "2") (pinfunction "2_2") (pintype "passive"))
    )
    (net (code "129") (name "Net-(LED12-PadA)") (class "Default")
      (node (ref "LED12") (pin "A") (pinfunction "A_A") (pintype "passive"))
      (node (ref "R260") (pin "2") (pinfunction "2_2") (pintype "passive"))
    )
    (net (code "130") (name "Net-(LED13-PadA)") (class "Default")
      (node (ref "LED13") (pin "A") (pinfunction "A_A") (pintype "passive"))
      (node (ref "R261") (pin "2") (pinfunction "2_2") (pintype "passive"))
    )
    (net (code "131") (name "Net-(LED14-PadA)") (class "Default")
      (node (ref "LED14") (pin "A") (pinfunction "A_A") (pintype "passive"))
      (node (ref "R262") (pin "1") (pinfunction "1_1") (pintype "passive"))
    )
    (net (code "132") (name "Net-(LED15-PadA)") (class "Default")
      (node (ref "LED15") (pin "A") (pinfunction "A_A") (pintype "passive"))
      (node (ref "R266") (pin "1") (pinfunction "1_1") (pintype "passive"))
    )
    (net (code "133") (name "Net-(LED16-PadA)") (class "Default")
      (node (ref "LED16") (pin "A") (pinfunction "A_A") (pintype "passive"))
      (node (ref "R267") (pin "2") (pinfunction "2_2") (pintype "passive"))
    )
    (net (code "134") (name "Net-(LED17-PadA)") (class "Default")
      (node (ref "LED17") (pin "A") (pinfunction "A_A") (pintype "passive"))
      (node (ref "R268") (pin "2") (pinfunction "2_2") (pintype "passive"))
    )
    (net (code "135") (name "Net-(LED18-PadA)") (class "Default")
      (node (ref "LED18") (pin "A") (pinfunction "A_A") (pintype "passive"))
      (node (ref "R238") (pin "1") (pinfunction "1_1") (pintype "passive"))
    )
    (net (code "136") (name "Net-(LED19-PadA)") (class "Default")
      (node (ref "LED19") (pin "A") (pinfunction "A_A") (pintype "passive"))
      (node (ref "R239") (pin "1") (pinfunction "1_1") (pintype "passive"))
    )
    (net (code "137") (name "Net-(LED20-PadA)") (class "Default")
      (node (ref "LED20") (pin "A") (pinfunction "A_A") (pintype "passive"))
      (node (ref "R245") (pin "1") (pinfunction "1_1") (pintype "passive"))
    )
    (net (code "138") (name "Net-(LED21-PadA)") (class "Default")
      (node (ref "LED21") (pin "A") (pinfunction "A_A") (pintype "passive"))
      (node (ref "R246") (pin "2") (pinfunction "2_2") (pintype "passive"))
    )
    (net (code "139") (name "Net-(LED22-PadA)") (class "Default")
      (node (ref "LED22") (pin "A") (pinfunction "A_A") (pintype "passive"))
      (node (ref "R248") (pin "2") (pinfunction "2_2") (pintype "passive"))
    )
    (net (code "140") (name "Net-(LED23-PadA)") (class "Default")
      (node (ref "LED23") (pin "A") (pinfunction "A_A") (pintype "passive"))
      (node (ref "R249") (pin "1") (pinfunction "1_1") (pintype "passive"))
    )
    (net (code "141") (name "Net-(LED24-PadA)") (class "Default")
      (node (ref "LED24") (pin "A") (pinfunction "A_A") (pintype "passive"))
      (node (ref "R258") (pin "2") (pinfunction "2_2") (pintype "passive"))
    )
    (net (code "142") (name "Net-(LED25-PadA)") (class "Default")
      (node (ref "LED25") (pin "A") (pinfunction "A_A") (pintype "passive"))
      (node (ref "R265") (pin "2") (pinfunction "2_2") (pintype "passive"))
    )
    (net (code "143") (name "Net-(LED26-PadA)") (class "Default")
      (node (ref "LED26") (pin "A") (pinfunction "A_A") (pintype "passive"))
      (node (ref "R264") (pin "2") (pinfunction "2_2") (pintype "passive"))
    )
    (net (code "144") (name "Net-(LED27-PadA)") (class "Default")
      (node (ref "LED27") (pin "A") (pinfunction "A_A") (pintype "passive"))
      (node (ref "R203") (pin "2") (pinfunction "2_2") (pintype "passive"))
    )
    (net (code "145") (name "Net-(LED28-PadA)") (class "Default")
      (node (ref "LED28") (pin "A") (pinfunction "A_A") (pintype "passive"))
      (node (ref "R229") (pin "2") (pinfunction "2_2") (pintype "passive"))
    )
    (net (code "146") (name "Net-(LED29-PadA)") (class "Default")
      (node (ref "LED29") (pin "A") (pinfunction "A_A") (pintype "passive"))
      (node (ref "R228") (pin "1") (pinfunction "1_1") (pintype "passive"))
    )
    (net (code "147") (name "Net-(LED30-PadA)") (class "Default")
      (node (ref "LED30") (pin "A") (pinfunction "A_A") (pintype "passive"))
      (node (ref "R227") (pin "2") (pinfunction "2_2") (pintype "passive"))
    )
    (net (code "148") (name "Net-(LED31-PadA)") (class "Default")
      (node (ref "LED31") (pin "A") (pinfunction "A_A") (pintype "passive"))
      (node (ref "R223") (pin "2") (pinfunction "2_2") (pintype "passive"))
    )
    (net (code "149") (name "Net-(LED32-PadA)") (class "Default")
      (node (ref "LED32") (pin "A") (pinfunction "A_A") (pintype "passive"))
      (node (ref "R222") (pin "1") (pinfunction "1_1") (pintype "passive"))
    )
    (net (code "150") (name "Net-(LED33-PadA)") (class "Default")
      (node (ref "LED33") (pin "A") (pinfunction "A_A") (pintype "passive"))
      (node (ref "R221") (pin "2") (pinfunction "2_2") (pintype "passive"))
    )
    (net (code "151") (name "Net-(LED34-PadA)") (class "Default")
      (node (ref "LED34") (pin "A") (pinfunction "A_A") (pintype "passive"))
      (node (ref "R217") (pin "1") (pinfunction "1_1") (pintype "passive"))
    )
    (net (code "152") (name "Net-(LED35-PadA)") (class "Default")
      (node (ref "LED35") (pin "A") (pinfunction "A_A") (pintype "passive"))
      (node (ref "R215") (pin "2") (pinfunction "2_2") (pintype "passive"))
    )
    (net (code "153") (name "Net-(LED36-PadA)") (class "Default")
      (node (ref "LED36") (pin "A") (pinfunction "A_A") (pintype "passive"))
      (node (ref "R213") (pin "2") (pinfunction "2_2") (pintype "passive"))
    )
    (net (code "154") (name "Net-(LED37-PadA)") (class "Default")
      (node (ref "LED37") (pin "A") (pinfunction "A_A") (pintype "passive"))
      (node (ref "R211") (pin "2") (pinfunction "2_2") (pintype "passive"))
    )
    (net (code "155") (name "Net-(LED38-PadA)") (class "Default")
      (node (ref "LED38") (pin "A") (pinfunction "A_A") (pintype "passive"))
      (node (ref "R208") (pin "2") (pinfunction "2_2") (pintype "passive"))
    )
    (net (code "156") (name "Net-(LED39-PadA)") (class "Default")
      (node (ref "LED39") (pin "A") (pinfunction "A_A") (pintype "passive"))
      (node (ref "R205") (pin "2") (pinfunction "2_2") (pintype "passive"))
    )
    (net (code "157") (name "Net-(LED40-PadA)") (class "Default")
      (node (ref "LED40") (pin "A") (pinfunction "A_A") (pintype "passive"))
      (node (ref "R204") (pin "1") (pinfunction "1_1") (pintype "passive"))
    )
    (net (code "158") (name "Net-(Q5-B)") (class "Default")
      (node (ref "Q5") (pin "1") (pinfunction "B_1") (pintype "passive"))
      (node (ref "R254") (pin "1") (pinfunction "1_1") (pintype "passive"))
      (node (ref "R255") (pin "2") (pinfunction "2_2") (pintype "passive"))
    )
    (net (code "159") (name "Net-(Q5-C)") (class "Default")
      (node (ref "Q5") (pin "2") (pinfunction "C_2") (pintype "passive"))
      (node (ref "S4") (pin "C") (pinfunction "C_C") (pintype "passive"))
    )
    (net (code "160") (name "Net-(R235-Pad1)") (class "Default")
      (node (ref "R235") (pin "1") (pinfunction "1_1") (pintype "passive"))
      (node (ref "R270") (pin "1") (pinfunction "1_1") (pintype "passive"))
      (node (ref "S2") (pin "A") (pinfunction "A_A") (pintype "passive"))
    )
    (net (code "161") (name "Net-(R236-Pad1)") (class "Default")
      (node (ref "R236") (pin "1") (pinfunction "1_1") (pintype "passive"))
      (node (ref "R269") (pin "2") (pinfunction "2_2") (pintype "passive"))
      (node (ref "S2") (pin "B") (pinfunction "B_B") (pintype "passive"))
    )
    (net (code "162") (name "Net-(S3-1)") (class "Default")
      (node (ref "D7") (pin "C") (pinfunction "C_C") (pintype "passive"))
      (node (ref "S3") (pin "P$1") (pinfunction "1_P$1") (pintype "passive"))
    )
    (net (code "163") (name "Net-(S3-2)") (class "Default")
      (node (ref "D8") (pin "C") (pinfunction "C_C") (pintype "passive"))
      (node (ref "S3") (pin "P$2") (pinfunction "2_P$2") (pintype "passive"))
    )
    (net (code "164") (name "Net-(S3-4)") (class "Default")
      (node (ref "D9") (pin "C") (pinfunction "C_C") (pintype "passive"))
      (node (ref "S3") (pin "P$4") (pinfunction "4_P$4") (pintype "passive"))
    )
    (net (code "165") (name "Net-(S3-8)") (class "Default")
      (node (ref "D10") (pin "C") (pinfunction "C_C") (pintype "passive"))
      (node (ref "S3") (pin "P$8") (pinfunction "8_P$8") (pintype "passive"))
    )
    (net (code "166") (name "Net-(S4-1)") (class "Default")
      (node (ref "D3") (pin "C") (pinfunction "C_C") (pintype "passive"))
      (node (ref "S4") (pin "P$1") (pinfunction "1_P$1") (pintype "passive"))
    )
    (net (code "167") (name "Net-(S4-2)") (class "Default")
      (node (ref "D4") (pin "C") (pinfunction "C_C") (pintype "passive"))
      (node (ref "S4") (pin "P$2") (pinfunction "2_P$2") (pintype "passive"))
    )
    (net (code "168") (name "Net-(S4-4)") (class "Default")
      (node (ref "D5") (pin "C") (pinfunction "C_C") (pintype "passive"))
      (node (ref "S4") (pin "P$4") (pinfunction "4_P$4") (pintype "passive"))
    )
    (net (code "169") (name "Net-(S4-8)") (class "Default")
      (node (ref "D6") (pin "C") (pinfunction "C_C") (pintype "passive"))
      (node (ref "S4") (pin "P$8") (pinfunction "8_P$8") (pintype "passive"))
    )
    (net (code "170") (name "Net-(S6-S1)") (class "Default")
      (node (ref "R240") (pin "1") (pinfunction "1_1") (pintype "passive"))
      (node (ref "S6") (pin "2") (pinfunction "S1_2") (pintype "passive"))
    )
    (net (code "171") (name "Net-(S8-P1)") (class "Default")
      (node (ref "R247") (pin "1") (pinfunction "1_1") (pintype "passive"))
      (node (ref "S8") (pin "4") (pinfunction "P1_4") (pintype "passive"))
    )
    (net (code "172") (name "Net-(S10-P1)") (class "Default")
      (node (ref "R257") (pin "1") (pinfunction "1_1") (pintype "passive"))
      (node (ref "S10") (pin "4") (pinfunction "P1_4") (pintype "passive"))
    )
    (net (code "173") (name "Net-(S11-P1)") (class "Default")
      (node (ref "R259") (pin "1") (pinfunction "1_1") (pintype "passive"))
      (node (ref "S11") (pin "4") (pinfunction "P1_4") (pintype "passive"))
    )
    (net (code "174") (name "Net-(S13-S1)") (class "Default")
      (node (ref "R263") (pin "1") (pinfunction "1_1") (pintype "passive"))
      (node (ref "S13") (pin "2") (pinfunction "S1_2") (pintype "passive"))
    )
    (net (code "175") (name "Net-(S16-S1)") (class "Default")
      (node (ref "R231") (pin "1") (pinfunction "1_1") (pintype "passive"))
      (node (ref "S16") (pin "2") (pinfunction "S1_2") (pintype "passive"))
    )
    (net (code "176") (name "Net-(S23-P1)") (class "Default")
      (node (ref "R212") (pin "1") (pinfunction "1_1") (pintype "passive"))
      (node (ref "S23") (pin "4") (pinfunction "P1_4") (pintype "passive"))
    )
    (net (code "177") (name "Net-(S24-P1)") (class "Default")
      (node (ref "R210") (pin "1") (pinfunction "1_1") (pintype "passive"))
      (node (ref "S24") (pin "4") (pinfunction "P1_4") (pintype "passive"))
    )
    (net (code "178") (name "Net-(S25-S1)") (class "Default")
      (node (ref "R209") (pin "1") (pinfunction "1_1") (pintype "passive"))
      (node (ref "S25") (pin "2") (pinfunction "S1_2") (pintype "passive"))
    )
    (net (code "179") (name "Net-(S26-S1)") (class "Default")
      (node (ref "R206") (pin "1") (pinfunction "1_1") (pintype "passive"))
      (node (ref "S26") (pin "2") (pinfunction "S1_2") (pintype "passive"))
    )
    (net (code "180") (name "Net-(S27-P1)") (class "Default")
      (node (ref "R201") (pin "1") (pinfunction "1_1") (pintype "passive"))
      (node (ref "S27") (pin "4") (pinfunction "P1_4") (pintype "passive"))
    )
    (net (code "181") (name "unconnected-(IC1B-O-Pad6)") (class "Default")
      (node (ref "IC1") (pin "6") (pinfunction "O_6") (pintype "output"))
    )
    (net (code "182") (name "unconnected-(IC1D-O-Pad11)") (class "Default")
      (node (ref "IC1") (pin "11") (pinfunction "O_11") (pintype "output"))
    )
    (net (code "183") (name "unconnected-(IC3-(A14)PC6-Pad27)") (class "Default")
      (node (ref "IC3") (pin "27") (pinfunction "(A14)PC6_27") (pintype "bidirectional"))
    )
    (net (code "184") (name "unconnected-(IC3-(INT0)PD2-Pad12)") (class "Default")
      (node (ref "IC3") (pin "12") (pinfunction "(INT0)PD2_12") (pintype "bidirectional"))
    )
    (net (code "185") (name "unconnected-(IC3-(INT1)PD3-Pad13)") (class "Default")
      (node (ref "IC3") (pin "13") (pinfunction "(INT1)PD3_13") (pintype "bidirectional"))
    )
    (net (code "186") (name "unconnected-(IC3-(INT2)PE0-Pad31)") (class "Default")
      (node (ref "IC3") (pin "31") (pinfunction "(INT2)PE0_31") (pintype "bidirectional"))
    )
    (net (code "187") (name "unconnected-(IC3-(SS)PB4-Pad5)") (class "Default")
      (node (ref "IC3") (pin "5") (pinfunction "(SS)PB4_5") (pintype "bidirectional"))
    )
    (net (code "188") (name "unconnected-(IC3-(T1)PB1-Pad2)") (class "Default")
      (node (ref "IC3") (pin "2") (pinfunction "(T1)PB1_2") (pintype "bidirectional"))
    )
    (net (code "189") (name "unconnected-(IC8A-QH*-Pad9)") (class "Default")
      (node (ref "IC8") (pin "9") (pinfunction "QH*_9") (pintype "tri_state"))
    )
    (net (code "190") (name "unconnected-(IC9A-Q0-Pad2)") (class "Default")
      (node (ref "IC9") (pin "2") (pinfunction "Q0_2") (pintype "output"))
    )
    (net (code "191") (name "unconnected-(IC9A-Q1-Pad5)") (class "Default")
      (node (ref "IC9") (pin "5") (pinfunction "Q1_5") (pintype "output"))
    )
    (net (code "192") (name "unconnected-(IC9A-Q2-Pad7)") (class "Default")
      (node (ref "IC9") (pin "7") (pinfunction "Q2_7") (pintype "output"))
    )
    (net (code "193") (name "unconnected-(IC9A-Q3-Pad10)") (class "Default")
      (node (ref "IC9") (pin "10") (pinfunction "Q3_10") (pintype "output"))
    )
    (net (code "194") (name "unconnected-(IC9A-Q4-Pad12)") (class "Default")
      (node (ref "IC9") (pin "12") (pinfunction "Q4_12") (pintype "output"))
    )
    (net (code "195") (name "unconnected-(IC9A-Q5-Pad15)") (class "Default")
      (node (ref "IC9") (pin "15") (pinfunction "Q5_15") (pintype "output"))
    )
    (net (code "196") (name "unconnected-(IC16A-~{QH}-Pad7)") (class "Default")
      (node (ref "IC16") (pin "7") (pinfunction "~{QH}_7") (pintype "output"))
    )
    (net (code "197") (name "unconnected-(IC17A-~{QH}-Pad7)") (class "Default")
      (node (ref "IC17") (pin "7") (pinfunction "~{QH}_7") (pintype "output"))
    )
    (net (code "198") (name "unconnected-(IC18A-~{QH}-Pad7)") (class "Default")
      (node (ref "IC18") (pin "7") (pinfunction "~{QH}_7") (pintype "output"))
    )
    (net (code "199") (name "unconnected-(S5-P-Pad3)") (class "Default")
      (node (ref "S5") (pin "3") (pinfunction "P_3") (pintype "passive"))
    )
    (net (code "200") (name "unconnected-(S5-S-Pad1)") (class "Default")
      (node (ref "S5") (pin "1") (pinfunction "S_1") (pintype "passive"))
    )
    (net (code "201") (name "unconnected-(S6-P1-Pad4)") (class "Default")
      (node (ref "S6") (pin "4") (pinfunction "P1_4") (pintype "passive"))
    )
    (net (code "202") (name "unconnected-(S7-P1-Pad4)") (class "Default")
      (node (ref "S7") (pin "4") (pinfunction "P1_4") (pintype "passive"))
    )
    (net (code "203") (name "unconnected-(S7-S1-Pad2)") (class "Default")
      (node (ref "S7") (pin "2") (pinfunction "S1_2") (pintype "passive"))
    )
    (net (code "204") (name "unconnected-(S8-S1-Pad2)") (class "Default")
      (node (ref "S8") (pin "2") (pinfunction "S1_2") (pintype "passive"))
    )
    (net (code "205") (name "unconnected-(S9-P1-Pad4)") (class "Default")
      (node (ref "S9") (pin "4") (pinfunction "P1_4") (pintype "passive"))
    )
    (net (code "206") (name "unconnected-(S9-S1-Pad2)") (class "Default")
      (node (ref "S9") (pin "2") (pinfunction "S1_2") (pintype "passive"))
    )
    (net (code "207") (name "unconnected-(S10-S1-Pad2)") (class "Default")
      (node (ref "S10") (pin "2") (pinfunction "S1_2") (pintype "passive"))
    )
    (net (code "208") (name "unconnected-(S11-S1-Pad2)") (class "Default")
      (node (ref "S11") (pin "2") (pinfunction "S1_2") (pintype "passive"))
    )
    (net (code "209") (name "unconnected-(S12-P-Pad3)") (class "Default")
      (node (ref "S12") (pin "3") (pinfunction "P_3") (pintype "passive"))
    )
    (net (code "210") (name "unconnected-(S12-S1-Pad2)") (class "Default")
      (node (ref "S12") (pin "2") (pinfunction "S1_2") (pintype "passive"))
    )
    (net (code "211") (name "unconnected-(S13-P-Pad3)") (class "Default")
      (node (ref "S13") (pin "3") (pinfunction "P_3") (pintype "passive"))
    )
    (net (code "212") (name "unconnected-(S14-P1-Pad4)") (class "Default")
      (node (ref "S14") (pin "4") (pinfunction "P1_4") (pintype "passive"))
    )
    (net (code "213") (name "unconnected-(S14-S-Pad1)") (class "Default")
      (node (ref "S14") (pin "1") (pinfunction "S_1") (pintype "passive"))
    )
    (net (code "214") (name "unconnected-(S15-P-Pad3)") (class "Default")
      (node (ref "S15") (pin "3") (pinfunction "P_3") (pintype "passive"))
    )
    (net (code "215") (name "unconnected-(S15-S1-Pad2)") (class "Default")
      (node (ref "S15") (pin "2") (pinfunction "S1_2") (pintype "passive"))
    )
    (net (code "216") (name "unconnected-(S16-P-Pad3)") (class "Default")
      (node (ref "S16") (pin "3") (pinfunction "P_3") (pintype "passive"))
    )
    (net (code "217") (name "unconnected-(S17-P-Pad3)") (class "Default")
      (node (ref "S17") (pin "3") (pinfunction "P_3") (pintype "passive"))
    )
    (net (code "218") (name "unconnected-(S17-S-Pad1)") (class "Default")
      (node (ref "S17") (pin "1") (pinfunction "S_1") (pintype "passive"))
    )
    (net (code "219") (name "unconnected-(S18-P-Pad3)") (class "Default")
      (node (ref "S18") (pin "3") (pinfunction "P_3") (pintype "passive"))
    )
    (net (code "220") (name "unconnected-(S18-S-Pad1)") (class "Default")
      (node (ref "S18") (pin "1") (pinfunction "S_1") (pintype "passive"))
    )
    (net (code "221") (name "unconnected-(S19-P-Pad3)") (class "Default")
      (node (ref "S19") (pin "3") (pinfunction "P_3") (pintype "passive"))
    )
    (net (code "222") (name "unconnected-(S20-P-Pad3)") (class "Default")
      (node (ref "S20") (pin "3") (pinfunction "P_3") (pintype "passive"))
    )
    (net (code "223") (name "unconnected-(S20-S-Pad1)") (class "Default")
      (node (ref "S20") (pin "1") (pinfunction "S_1") (pintype "passive"))
    )
    (net (code "224") (name "unconnected-(S21-P-Pad3)") (class "Default")
      (node (ref "S21") (pin "3") (pinfunction "P_3") (pintype "passive"))
    )
    (net (code "225") (name "unconnected-(S21-S-Pad1)") (class "Default")
      (node (ref "S21") (pin "1") (pinfunction "S_1") (pintype "passive"))
    )
    (net (code "226") (name "unconnected-(S22-P-Pad3)") (class "Default")
      (node (ref "S22") (pin "3") (pinfunction "P_3") (pintype "passive"))
    )
    (net (code "227") (name "unconnected-(S24-S-Pad1)") (class "Default")
      (node (ref "S24") (pin "1") (pinfunction "S_1") (pintype "passive"))
    )
    (net (code "228") (name "unconnected-(S25-P-Pad3)") (class "Default")
      (node (ref "S25") (pin "3") (pinfunction "P_3") (pintype "passive"))
    )
    (net (code "229") (name "unconnected-(S26-P-Pad3)") (class "Default")
      (node (ref "S26") (pin "3") (pinfunction "P_3") (pintype "passive"))
    )
    (net (code "230") (name "unconnected-(S27-S-Pad1)") (class "Default")
      (node (ref "S27") (pin "1") (pinfunction "S_1") (pintype "passive"))
    )
  )
)
